# midimixer-channel-rev2.net
KiCad netlist of a schematic drawn in EAGLE
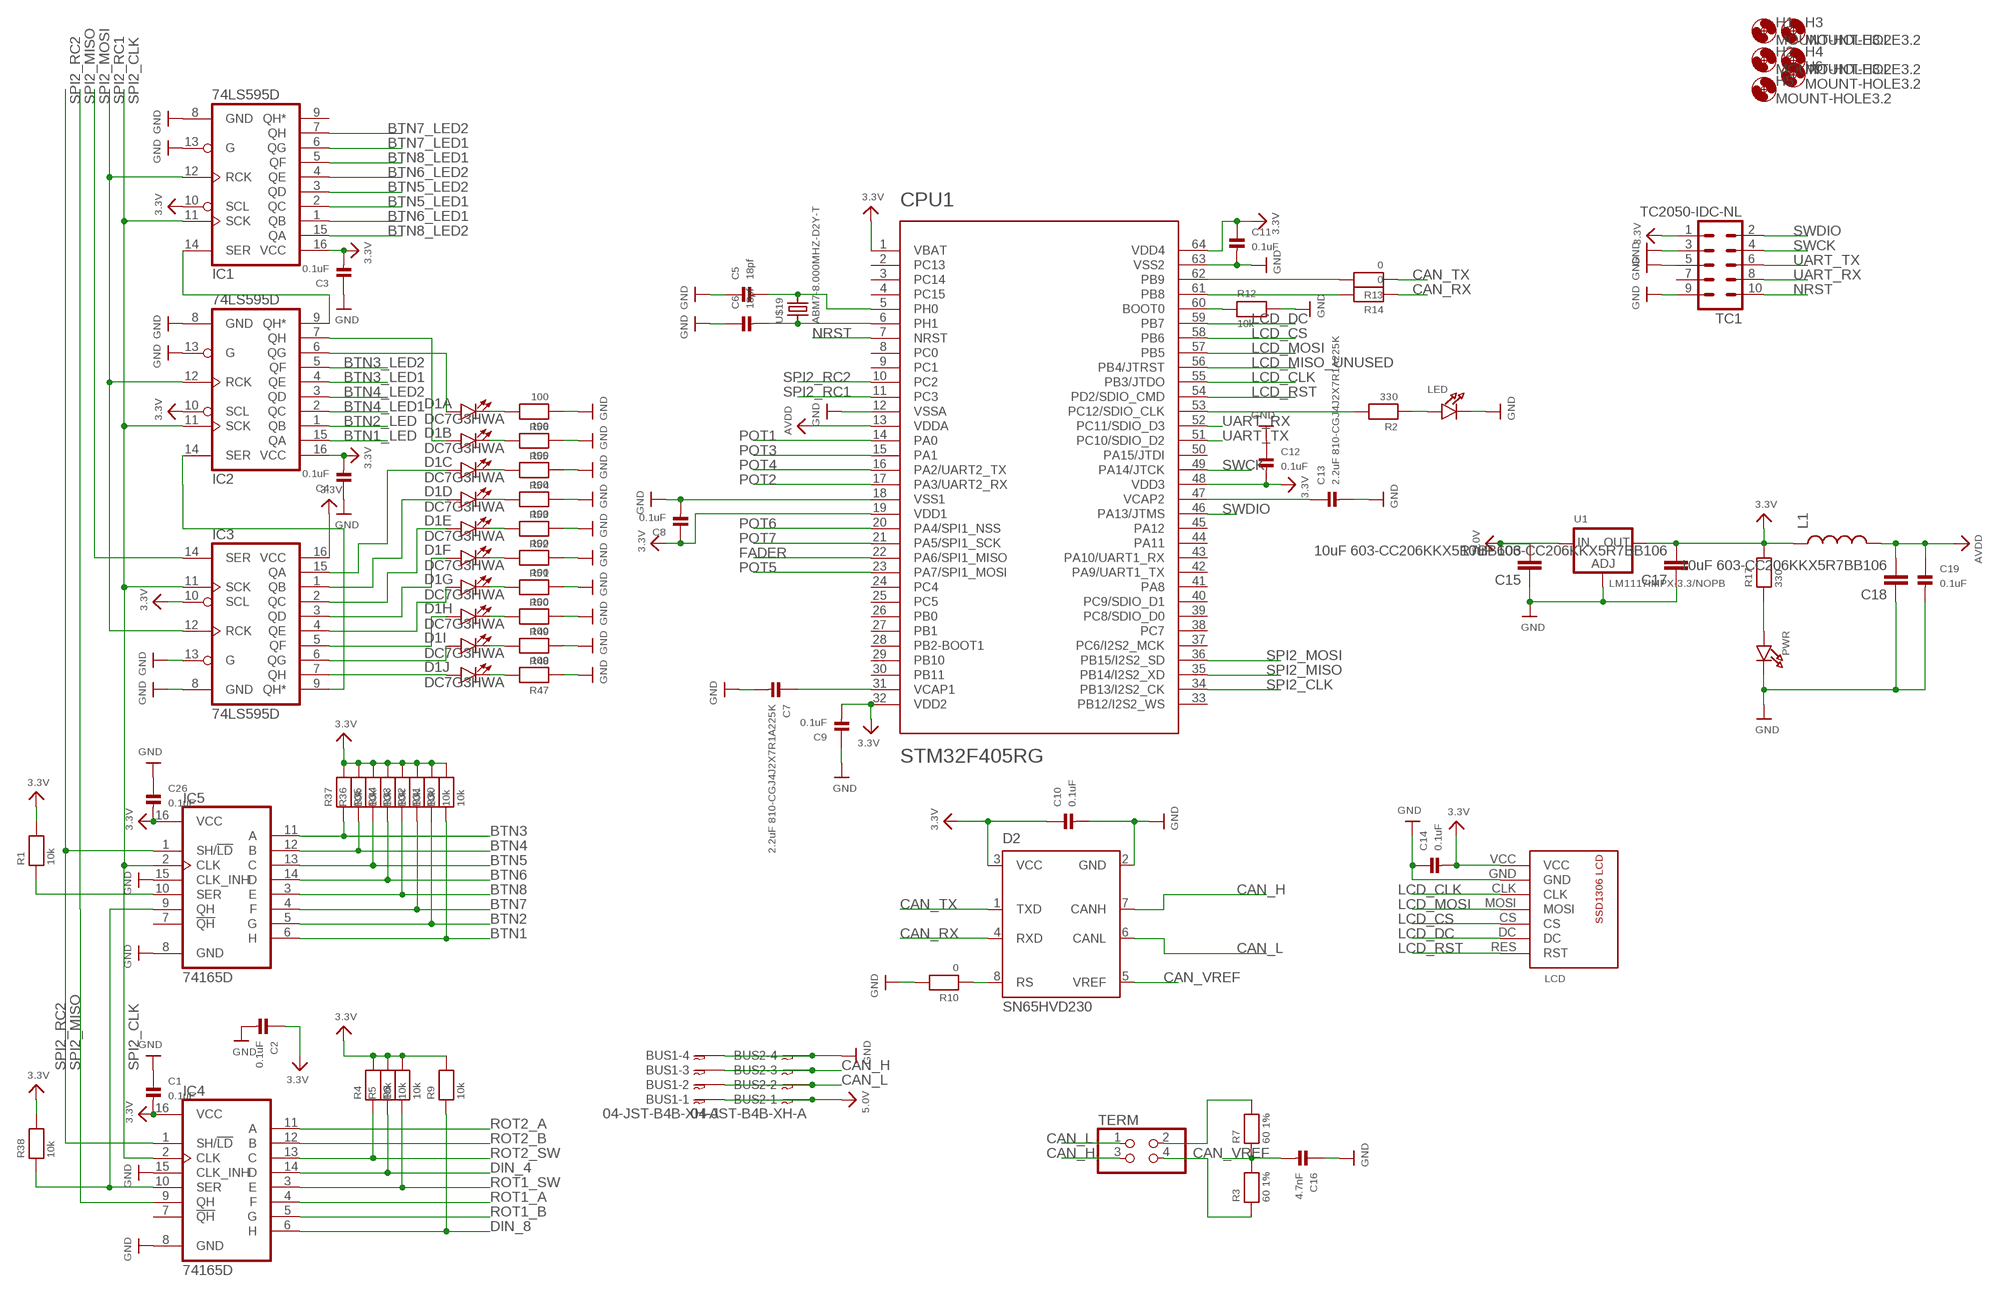
[diagram p0: schematic, sheet 1]
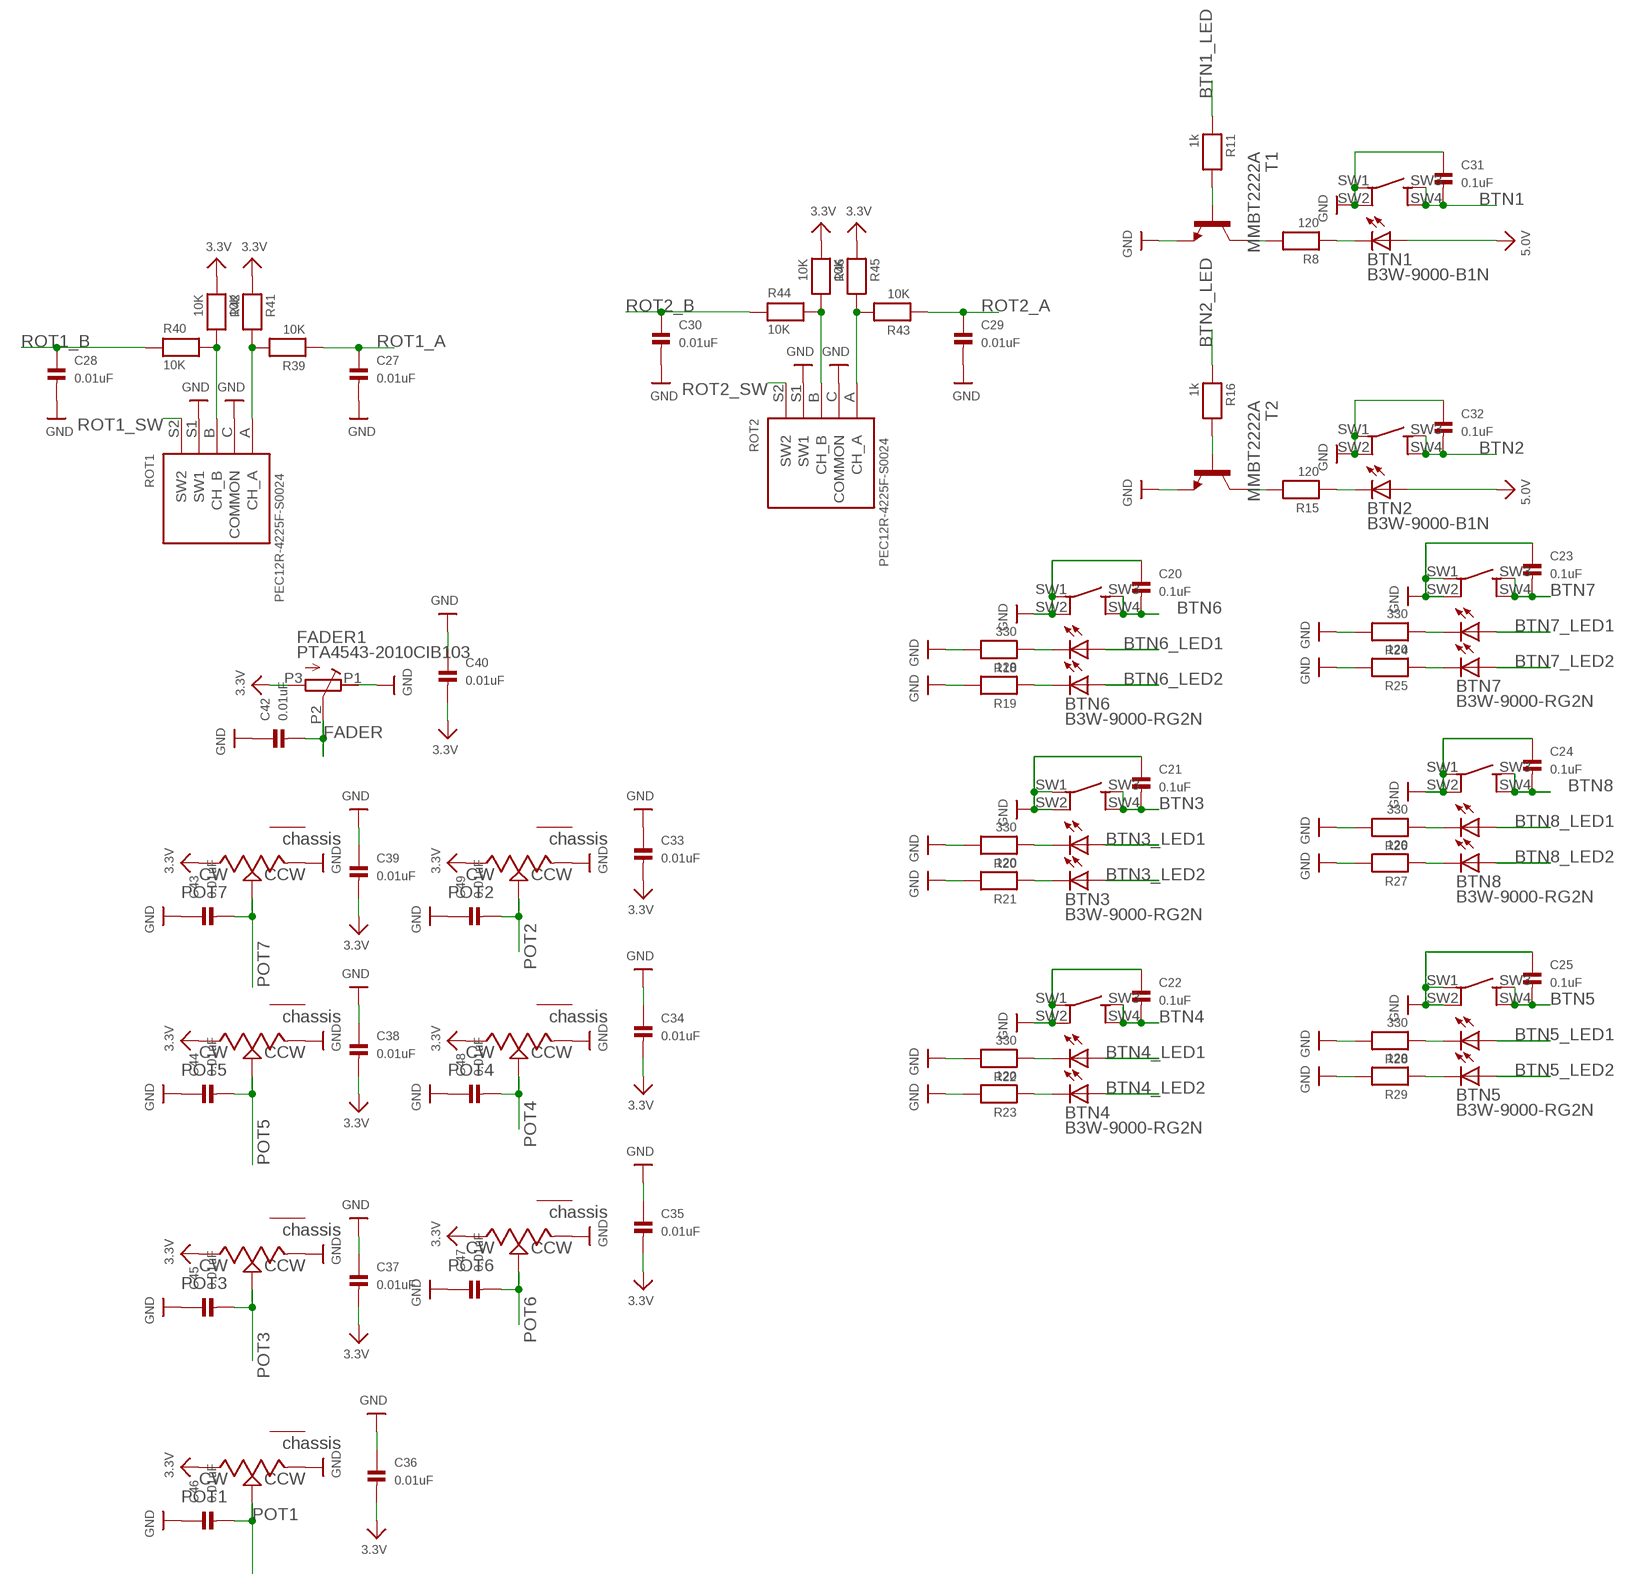
[diagram p1: schematic, sheet 2]

(export (version "E")
  (design (tool "Eeschema 10.0.6"))
  (components
    (comp (ref "BUS1")
      (value "04-JST-B4B-XH-A")
      (footprint "eagle-import:B4B-XH")
      (fields (field (name "MPN") "B4B-XH-A(LF)(SN)"))
      (libsource (lib "eagle-import") (part "04-JST-B4B-XH-A"))
    )
    (comp (ref "BUS2")
      (value "04-JST-B4B-XH-A")
      (footprint "eagle-import:B4B-XH")
      (fields (field (name "MPN") "B4B-XH-A(LF)(SN)"))
      (libsource (lib "eagle-import") (part "04-JST-B4B-XH-A"))
    )
    (comp (ref "C1")
      (value "0.1uF")
      (footprint "eagle-import:0603")
      (libsource (lib "eagle-import") (part "CAP_CERAMIC0603"))
    )
    (comp (ref "C2")
      (value "0.1uF")
      (footprint "eagle-import:0603")
      (libsource (lib "eagle-import") (part "CAP_CERAMIC0603"))
    )
    (comp (ref "C3")
      (value "0.1uF")
      (footprint "eagle-import:0603")
      (libsource (lib "eagle-import") (part "CAP_CERAMIC0603"))
    )
    (comp (ref "C4")
      (value "0.1uF")
      (footprint "eagle-import:0603")
      (libsource (lib "eagle-import") (part "CAP_CERAMIC0603"))
    )
    (comp (ref "C5")
      (value "18pf")
      (footprint "eagle-import:0603")
      (libsource (lib "eagle-import") (part "CAP_CERAMIC0603"))
    )
    (comp (ref "C6")
      (value "18pf")
      (footprint "eagle-import:0603")
      (libsource (lib "eagle-import") (part "CAP_CERAMIC0603"))
    )
    (comp (ref "C7")
      (value "2.2uF 810-CGJ4J2X7R1A225K")
      (footprint "eagle-import:0805")
      (fields (field (name "MPN") "CGJ4J2X7R1A225K125AA"))
      (libsource (lib "eagle-import") (part "CAP_CERAMIC0805"))
    )
    (comp (ref "C8")
      (value "0.1uF")
      (footprint "eagle-import:0603")
      (libsource (lib "eagle-import") (part "CAP_CERAMIC0603"))
    )
    (comp (ref "C9")
      (value "0.1uF")
      (footprint "eagle-import:0603")
      (libsource (lib "eagle-import") (part "CAP_CERAMIC0603"))
    )
    (comp (ref "C10")
      (value "0.1uF")
      (footprint "eagle-import:0603")
      (libsource (lib "eagle-import") (part "CAP_CERAMIC0603"))
    )
    (comp (ref "C11")
      (value "0.1uF")
      (footprint "eagle-import:0603")
      (libsource (lib "eagle-import") (part "CAP_CERAMIC0603"))
    )
    (comp (ref "C12")
      (value "0.1uF")
      (footprint "eagle-import:0603")
      (libsource (lib "eagle-import") (part "CAP_CERAMIC0603"))
    )
    (comp (ref "C13")
      (value "2.2uF 810-CGJ4J2X7R1A225K")
      (footprint "eagle-import:0805")
      (fields (field (name "MPN") "CGJ4J2X7R1A225K125AA"))
      (libsource (lib "eagle-import") (part "CAP_CERAMIC0805"))
    )
    (comp (ref "C14")
      (value "0.1uF")
      (footprint "eagle-import:0603")
      (libsource (lib "eagle-import") (part "CAP_CERAMIC0603"))
    )
    (comp (ref "C15")
      (value "10uF 603-CC206KKX5R7BB106")
      (footprint "eagle-import:1206")
      (fields (field (name "MPN") "CC1206KKX5R7BB106"))
      (libsource (lib "eagle-import") (part "CAP1206"))
    )
    (comp (ref "C16")
      (value "4.7nF")
      (footprint "eagle-import:0603")
      (libsource (lib "eagle-import") (part "CAP_CERAMIC0603"))
    )
    (comp (ref "C17")
      (value "10uF 603-CC206KKX5R7BB106")
      (footprint "eagle-import:1206")
      (fields (field (name "MPN") "CC1206KKX5R7BB106"))
      (libsource (lib "eagle-import") (part "CAP1206"))
    )
    (comp (ref "C18")
      (value "10uF 603-CC206KKX5R7BB106")
      (footprint "eagle-import:1206")
      (fields (field (name "MPN") "CC1206KKX5R7BB106"))
      (libsource (lib "eagle-import") (part "CAP1206"))
    )
    (comp (ref "C19")
      (value "0.1uF")
      (footprint "eagle-import:0603")
      (libsource (lib "eagle-import") (part "CAP_CERAMIC0603"))
    )
    (comp (ref "C26")
      (value "0.1uF")
      (footprint "eagle-import:0603")
      (libsource (lib "eagle-import") (part "CAP_CERAMIC0603"))
    )
    (comp (ref "CPU1")
      (value "STM32F405RG")
      (footprint "eagle-import:TQFP64")
      (fields (field (name "MPN") "STM32F405RGT6"))
      (libsource (lib "eagle-import") (part "STM32F405RG"))
    )
    (comp (ref "D1")
      (value "DC7G3HWA")
      (footprint "eagle-import:LED_BARGAPH_10")
      (libsource (lib "eagle-import") (part "LED_BARGRAPH_10"))
    )
    (comp (ref "D2")
      (value "SN65HVD230")
      (footprint "eagle-import:SO8")
      (fields (field (name "MPN") "SN65HVD230DR"))
      (libsource (lib "eagle-import") (part "SN65HVD230"))
    )
    (comp (ref "H1")
      (value "MOUNT-HOLE3.2")
      (footprint "eagle-import:3,2")
      (libsource (lib "eagle-import") (part "MOUNT-HOLE3.2"))
    )
    (comp (ref "H2")
      (value "MOUNT-HOLE3.2")
      (footprint "eagle-import:3,2")
      (libsource (lib "eagle-import") (part "MOUNT-HOLE3.2"))
    )
    (comp (ref "H3")
      (value "MOUNT-HOLE3.2")
      (footprint "eagle-import:3,2")
      (libsource (lib "eagle-import") (part "MOUNT-HOLE3.2"))
    )
    (comp (ref "H4")
      (value "MOUNT-HOLE3.2")
      (footprint "eagle-import:3,2")
      (libsource (lib "eagle-import") (part "MOUNT-HOLE3.2"))
    )
    (comp (ref "H5")
      (value "MOUNT-HOLE3.2")
      (footprint "eagle-import:3,2")
      (libsource (lib "eagle-import") (part "MOUNT-HOLE3.2"))
    )
    (comp (ref "H6")
      (value "MOUNT-HOLE3.2")
      (footprint "eagle-import:3,2")
      (libsource (lib "eagle-import") (part "MOUNT-HOLE3.2"))
    )
    (comp (ref "IC1")
      (value "74LS595D")
      (footprint "eagle-import:SO16")
      (fields (field (name "MPN") "74HC595D,118"))
      (libsource (lib "eagle-import") (part "74595DLS"))
    )
    (comp (ref "IC2")
      (value "74LS595D")
      (footprint "eagle-import:SO16")
      (fields (field (name "MPN") "74HC595D,118"))
      (libsource (lib "eagle-import") (part "74595DLS"))
    )
    (comp (ref "IC3")
      (value "74LS595D")
      (footprint "eagle-import:SO16")
      (fields (field (name "MPN") "74HC595D,118"))
      (libsource (lib "eagle-import") (part "74595DLS"))
    )
    (comp (ref "IC4")
      (value "74165D")
      (footprint "eagle-import:SO16")
      (fields (field (name "MPN") "74HC165D,653"))
      (libsource (lib "eagle-import") (part "74165D"))
    )
    (comp (ref "IC5")
      (value "74165D")
      (footprint "eagle-import:SO16")
      (fields (field (name "MPN") "74HC165D,653"))
      (libsource (lib "eagle-import") (part "74165D"))
    )
    (comp (ref "L1")
      (value "INDUCTOR0805")
      (footprint "eagle-import:0805")
      (fields (field (name "MPN") "2508056017Y2"))
      (libsource (lib "eagle-import") (part "INDUCTOR0805"))
    )
    (comp (ref "LCD")
      (value "SSD1306-7PINWITHOUT-HOLES")
      (footprint "eagle-import:SSD1306-7PIN-NO-HOLES")
      (libsource (lib "eagle-import") (part "SSD1306-7PINWITHOUT-HOLES"))
    )
    (comp (ref "LED")
      (value "LED0603")
      (footprint "eagle-import:CHIPLED_0603")
      (fields (field (name "MPN") "MF-LED-0603-GREEN"))
      (libsource (lib "eagle-import") (part "LED0603"))
    )
    (comp (ref "PWR")
      (value "LED0603")
      (footprint "eagle-import:CHIPLED_0603")
      (fields (field (name "MPN") "MF-LED-0603-GREEN"))
      (libsource (lib "eagle-import") (part "LED0603"))
    )
    (comp (ref "R1")
      (value "10k")
      (footprint "eagle-import:_0603")
      (libsource (lib "eagle-import") (part "RESISTOR_0603"))
    )
    (comp (ref "R2")
      (value "330")
      (footprint "eagle-import:0603")
      (libsource (lib "eagle-import") (part "RESISTOR0603"))
    )
    (comp (ref "R3")
      (value "60 1%")
      (footprint "eagle-import:0603")
      (fields (field (name "MPN") "MF-RES-0603-60.4"))
      (libsource (lib "eagle-import") (part "RESISTOR0603"))
    )
    (comp (ref "R4")
      (value "10k")
      (footprint "eagle-import:_0603")
      (libsource (lib "eagle-import") (part "RESISTOR_0603"))
    )
    (comp (ref "R5")
      (value "10k")
      (footprint "eagle-import:_0603")
      (libsource (lib "eagle-import") (part "RESISTOR_0603"))
    )
    (comp (ref "R6")
      (value "10k")
      (footprint "eagle-import:_0603")
      (libsource (lib "eagle-import") (part "RESISTOR_0603"))
    )
    (comp (ref "R7")
      (value "60 1%")
      (footprint "eagle-import:0603")
      (fields (field (name "MPN") "MF-RES-0603-60.4"))
      (libsource (lib "eagle-import") (part "RESISTOR0603"))
    )
    (comp (ref "R9")
      (value "10k")
      (footprint "eagle-import:_0603")
      (libsource (lib "eagle-import") (part "RESISTOR_0603"))
    )
    (comp (ref "R10")
      (value "0")
      (footprint "eagle-import:_0603")
      (libsource (lib "eagle-import") (part "RESISTOR_0603"))
    )
    (comp (ref "R12")
      (value "10k")
      (footprint "eagle-import:_0603")
      (libsource (lib "eagle-import") (part "RESISTOR_0603"))
    )
    (comp (ref "R13")
      (value "0")
      (footprint "eagle-import:_0603")
      (libsource (lib "eagle-import") (part "RESISTOR_0603"))
    )
    (comp (ref "R14")
      (value "0")
      (footprint "eagle-import:_0603")
      (libsource (lib "eagle-import") (part "RESISTOR_0603"))
    )
    (comp (ref "R17")
      (value "330")
      (footprint "eagle-import:0603")
      (libsource (lib "eagle-import") (part "RESISTOR0603"))
    )
    (comp (ref "R30")
      (value "10k")
      (footprint "eagle-import:_0603")
      (libsource (lib "eagle-import") (part "RESISTOR_0603"))
    )
    (comp (ref "R31")
      (value "10k")
      (footprint "eagle-import:_0603")
      (libsource (lib "eagle-import") (part "RESISTOR_0603"))
    )
    (comp (ref "R32")
      (value "10k")
      (footprint "eagle-import:_0603")
      (libsource (lib "eagle-import") (part "RESISTOR_0603"))
    )
    (comp (ref "R33")
      (value "10k")
      (footprint "eagle-import:_0603")
      (libsource (lib "eagle-import") (part "RESISTOR_0603"))
    )
    (comp (ref "R34")
      (value "10k")
      (footprint "eagle-import:_0603")
      (libsource (lib "eagle-import") (part "RESISTOR_0603"))
    )
    (comp (ref "R35")
      (value "10k")
      (footprint "eagle-import:_0603")
      (libsource (lib "eagle-import") (part "RESISTOR_0603"))
    )
    (comp (ref "R36")
      (value "10k")
      (footprint "eagle-import:_0603")
      (libsource (lib "eagle-import") (part "RESISTOR_0603"))
    )
    (comp (ref "R37")
      (value "10k")
      (footprint "eagle-import:_0603")
      (libsource (lib "eagle-import") (part "RESISTOR_0603"))
    )
    (comp (ref "R38")
      (value "10k")
      (footprint "eagle-import:_0603")
      (libsource (lib "eagle-import") (part "RESISTOR_0603"))
    )
    (comp (ref "R47")
      (value "100")
      (footprint "eagle-import:_0603")
      (libsource (lib "eagle-import") (part "RESISTOR_0603"))
    )
    (comp (ref "R48")
      (value "100")
      (footprint "eagle-import:_0603")
      (libsource (lib "eagle-import") (part "RESISTOR_0603"))
    )
    (comp (ref "R49")
      (value "100")
      (footprint "eagle-import:_0603")
      (libsource (lib "eagle-import") (part "RESISTOR_0603"))
    )
    (comp (ref "R50")
      (value "100")
      (footprint "eagle-import:_0603")
      (libsource (lib "eagle-import") (part "RESISTOR_0603"))
    )
    (comp (ref "R51")
      (value "100")
      (footprint "eagle-import:_0603")
      (libsource (lib "eagle-import") (part "RESISTOR_0603"))
    )
    (comp (ref "R52")
      (value "100")
      (footprint "eagle-import:_0603")
      (libsource (lib "eagle-import") (part "RESISTOR_0603"))
    )
    (comp (ref "R53")
      (value "100")
      (footprint "eagle-import:_0603")
      (libsource (lib "eagle-import") (part "RESISTOR_0603"))
    )
    (comp (ref "R54")
      (value "100")
      (footprint "eagle-import:_0603")
      (libsource (lib "eagle-import") (part "RESISTOR_0603"))
    )
    (comp (ref "R55")
      (value "100")
      (footprint "eagle-import:_0603")
      (libsource (lib "eagle-import") (part "RESISTOR_0603"))
    )
    (comp (ref "R56")
      (value "100")
      (footprint "eagle-import:_0603")
      (libsource (lib "eagle-import") (part "RESISTOR_0603"))
    )
    (comp (ref "TC1")
      (value "TC2050-IDC-NL")
      (footprint "eagle-import:TC2050-IDC-NL")
      (libsource (lib "eagle-import") (part "TC2050-IDC-NL"))
    )
    (comp (ref "TERM")
      (value "PINHD-2X2")
      (footprint "eagle-import:2X02")
      (fields (field (name "MPN") "5-146254-2"))
      (libsource (lib "eagle-import") (part "PINHD-2X2"))
    )
    (comp (ref "U$19")
      (value "ABM7-8.000MHZ-D2Y-T")
      (footprint "eagle-import:ABM7-8.000MHZ-D2Y-T")
      (libsource (lib "eagle-import") (part "ABM7-8.000MHZ-D2Y-T"))
    )
    (comp (ref "U1")
      (value "LM1117IMPX-3.3/NOPB")
      (footprint "eagle-import:SOT223-R")
      (fields (field (name "MPN") "LM1117MPX-3.3/NOPB"))
      (libsource (lib "eagle-import") (part "LM1117SOT223-REFLOW"))
    )
    (comp (ref "BTN1")
      (value "B3W-9000-B1N")
      (footprint "eagle-import:B3W-9000-X1X")
      (libsource (lib "eagle-import") (part "B3W-9000-B1N"))
    )
    (comp (ref "BTN2")
      (value "B3W-9000-B1N")
      (footprint "eagle-import:B3W-9000-X1X")
      (libsource (lib "eagle-import") (part "B3W-9000-B1N"))
    )
    (comp (ref "BTN3")
      (value "B3W-9000-RG2N")
      (footprint "eagle-import:B3W-9000-X2X")
      (libsource (lib "eagle-import") (part "B3W-9000-RG2N"))
    )
    (comp (ref "BTN4")
      (value "B3W-9000-RG2N")
      (footprint "eagle-import:B3W-9000-X2X")
      (libsource (lib "eagle-import") (part "B3W-9000-RG2N"))
    )
    (comp (ref "BTN5")
      (value "B3W-9000-RG2N")
      (footprint "eagle-import:B3W-9000-X2X")
      (libsource (lib "eagle-import") (part "B3W-9000-RG2N"))
    )
    (comp (ref "BTN6")
      (value "B3W-9000-RG2N")
      (footprint "eagle-import:B3W-9000-X2X")
      (libsource (lib "eagle-import") (part "B3W-9000-RG2N"))
    )
    (comp (ref "BTN7")
      (value "B3W-9000-RG2N")
      (footprint "eagle-import:B3W-9000-X2X")
      (libsource (lib "eagle-import") (part "B3W-9000-RG2N"))
    )
    (comp (ref "BTN8")
      (value "B3W-9000-RG2N")
      (footprint "eagle-import:B3W-9000-X2X")
      (libsource (lib "eagle-import") (part "B3W-9000-RG2N"))
    )
    (comp (ref "C20")
      (value "0.1uF")
      (footprint "eagle-import:0603")
      (libsource (lib "eagle-import") (part "CAP_CERAMIC0603"))
    )
    (comp (ref "C21")
      (value "0.1uF")
      (footprint "eagle-import:0603")
      (libsource (lib "eagle-import") (part "CAP_CERAMIC0603"))
    )
    (comp (ref "C22")
      (value "0.1uF")
      (footprint "eagle-import:0603")
      (libsource (lib "eagle-import") (part "CAP_CERAMIC0603"))
    )
    (comp (ref "C23")
      (value "0.1uF")
      (footprint "eagle-import:0603")
      (libsource (lib "eagle-import") (part "CAP_CERAMIC0603"))
    )
    (comp (ref "C24")
      (value "0.1uF")
      (footprint "eagle-import:0603")
      (libsource (lib "eagle-import") (part "CAP_CERAMIC0603"))
    )
    (comp (ref "C25")
      (value "0.1uF")
      (footprint "eagle-import:0603")
      (libsource (lib "eagle-import") (part "CAP_CERAMIC0603"))
    )
    (comp (ref "C27")
      (value "0.01uF")
      (footprint "eagle-import:0603")
      (libsource (lib "eagle-import") (part "CAP_CERAMIC0603"))
    )
    (comp (ref "C28")
      (value "0.01uF")
      (footprint "eagle-import:0603")
      (libsource (lib "eagle-import") (part "CAP_CERAMIC0603"))
    )
    (comp (ref "C29")
      (value "0.01uF")
      (footprint "eagle-import:0603")
      (libsource (lib "eagle-import") (part "CAP_CERAMIC0603"))
    )
    (comp (ref "C30")
      (value "0.01uF")
      (footprint "eagle-import:0603")
      (libsource (lib "eagle-import") (part "CAP_CERAMIC0603"))
    )
    (comp (ref "C31")
      (value "0.1uF")
      (footprint "eagle-import:0603")
      (libsource (lib "eagle-import") (part "CAP_CERAMIC0603"))
    )
    (comp (ref "C32")
      (value "0.1uF")
      (footprint "eagle-import:0603")
      (libsource (lib "eagle-import") (part "CAP_CERAMIC0603"))
    )
    (comp (ref "C33")
      (value "0.01uF")
      (footprint "eagle-import:0603")
      (libsource (lib "eagle-import") (part "CAP_CERAMIC0603"))
    )
    (comp (ref "C34")
      (value "0.01uF")
      (footprint "eagle-import:0603")
      (libsource (lib "eagle-import") (part "CAP_CERAMIC0603"))
    )
    (comp (ref "C35")
      (value "0.01uF")
      (footprint "eagle-import:0603")
      (libsource (lib "eagle-import") (part "CAP_CERAMIC0603"))
    )
    (comp (ref "C36")
      (value "0.01uF")
      (footprint "eagle-import:0603")
      (libsource (lib "eagle-import") (part "CAP_CERAMIC0603"))
    )
    (comp (ref "C37")
      (value "0.01uF")
      (footprint "eagle-import:0603")
      (libsource (lib "eagle-import") (part "CAP_CERAMIC0603"))
    )
    (comp (ref "C38")
      (value "0.01uF")
      (footprint "eagle-import:0603")
      (libsource (lib "eagle-import") (part "CAP_CERAMIC0603"))
    )
    (comp (ref "C39")
      (value "0.01uF")
      (footprint "eagle-import:0603")
      (libsource (lib "eagle-import") (part "CAP_CERAMIC0603"))
    )
    (comp (ref "C40")
      (value "0.01uF")
      (footprint "eagle-import:0603")
      (libsource (lib "eagle-import") (part "CAP_CERAMIC0603"))
    )
    (comp (ref "C42")
      (value "0.01uF")
      (footprint "eagle-import:0603")
      (libsource (lib "eagle-import") (part "CAP_CERAMIC0603"))
    )
    (comp (ref "C43")
      (value "0.01uF")
      (footprint "eagle-import:0603")
      (libsource (lib "eagle-import") (part "CAP_CERAMIC0603"))
    )
    (comp (ref "C44")
      (value "0.01uF")
      (footprint "eagle-import:0603")
      (libsource (lib "eagle-import") (part "CAP_CERAMIC0603"))
    )
    (comp (ref "C45")
      (value "0.01uF")
      (footprint "eagle-import:0603")
      (libsource (lib "eagle-import") (part "CAP_CERAMIC0603"))
    )
    (comp (ref "C46")
      (value "0.01uF")
      (footprint "eagle-import:0603")
      (libsource (lib "eagle-import") (part "CAP_CERAMIC0603"))
    )
    (comp (ref "C47")
      (value "0.01uF")
      (footprint "eagle-import:0603")
      (libsource (lib "eagle-import") (part "CAP_CERAMIC0603"))
    )
    (comp (ref "C48")
      (value "0.01uF")
      (footprint "eagle-import:0603")
      (libsource (lib "eagle-import") (part "CAP_CERAMIC0603"))
    )
    (comp (ref "C49")
      (value "0.01uF")
      (footprint "eagle-import:0603")
      (libsource (lib "eagle-import") (part "CAP_CERAMIC0603"))
    )
    (comp (ref "FADER1")
      (value "PTA4543-2010CIB103")
      (footprint "eagle-import:PTA4543-2015CPB103")
      (libsource (lib "eagle-import") (part "PTA4543-2015CPB103"))
    )
    (comp (ref "POT1")
      (value "POTENTIOMETERPTV09A_VERTICAL")
      (footprint "eagle-import:PTV09A-4")
      (fields (field (name "MPN") "PTV09A-4225F-B203"))
      (libsource (lib "eagle-import") (part "POTENTIOMETERPTV09A_VERTICAL"))
    )
    (comp (ref "POT2")
      (value "POTENTIOMETERPTV09A_VERTICAL")
      (footprint "eagle-import:PTV09A-4")
      (fields (field (name "MPN") "PTV09A-4225F-B203"))
      (libsource (lib "eagle-import") (part "POTENTIOMETERPTV09A_VERTICAL"))
    )
    (comp (ref "POT3")
      (value "POTENTIOMETERPTV09A_VERTICAL")
      (footprint "eagle-import:PTV09A-4")
      (fields (field (name "MPN") "PTV09A-4225F-B203"))
      (libsource (lib "eagle-import") (part "POTENTIOMETERPTV09A_VERTICAL"))
    )
    (comp (ref "POT4")
      (value "POTENTIOMETERPTV09A_VERTICAL")
      (footprint "eagle-import:PTV09A-4")
      (fields (field (name "MPN") "PTV09A-4225F-B203"))
      (libsource (lib "eagle-import") (part "POTENTIOMETERPTV09A_VERTICAL"))
    )
    (comp (ref "POT5")
      (value "POTENTIOMETERPTV09A_VERTICAL")
      (footprint "eagle-import:PTV09A-4")
      (fields (field (name "MPN") "PTV09A-4225F-B203"))
      (libsource (lib "eagle-import") (part "POTENTIOMETERPTV09A_VERTICAL"))
    )
    (comp (ref "POT6")
      (value "POTENTIOMETERPTV09A_VERTICAL")
      (footprint "eagle-import:PTV09A-4")
      (fields (field (name "MPN") "PTV09A-4225F-B203"))
      (libsource (lib "eagle-import") (part "POTENTIOMETERPTV09A_VERTICAL"))
    )
    (comp (ref "POT7")
      (value "POTENTIOMETERPTV09A_VERTICAL")
      (footprint "eagle-import:PTV09A-4")
      (fields (field (name "MPN") "PTV09A-4225F-B203"))
      (libsource (lib "eagle-import") (part "POTENTIOMETERPTV09A_VERTICAL"))
    )
    (comp (ref "R8")
      (value "120")
      (footprint "eagle-import:0603")
      (libsource (lib "eagle-import") (part "RESISTOR0603"))
    )
    (comp (ref "R11")
      (value "1k")
      (footprint "eagle-import:0603")
      (libsource (lib "eagle-import") (part "RESISTOR0603"))
    )
    (comp (ref "R15")
      (value "120")
      (footprint "eagle-import:0603")
      (libsource (lib "eagle-import") (part "RESISTOR0603"))
    )
    (comp (ref "R16")
      (value "1k")
      (footprint "eagle-import:0603")
      (libsource (lib "eagle-import") (part "RESISTOR0603"))
    )
    (comp (ref "R18")
      (value "330")
      (footprint "eagle-import:0603")
      (libsource (lib "eagle-import") (part "RESISTOR0603"))
    )
    (comp (ref "R19")
      (value "120")
      (footprint "eagle-import:0603")
      (libsource (lib "eagle-import") (part "RESISTOR0603"))
    )
    (comp (ref "R20")
      (value "330")
      (footprint "eagle-import:0603")
      (libsource (lib "eagle-import") (part "RESISTOR0603"))
    )
    (comp (ref "R21")
      (value "120")
      (footprint "eagle-import:0603")
      (libsource (lib "eagle-import") (part "RESISTOR0603"))
    )
    (comp (ref "R22")
      (value "330")
      (footprint "eagle-import:0603")
      (libsource (lib "eagle-import") (part "RESISTOR0603"))
    )
    (comp (ref "R23")
      (value "120")
      (footprint "eagle-import:0603")
      (libsource (lib "eagle-import") (part "RESISTOR0603"))
    )
    (comp (ref "R24")
      (value "330")
      (footprint "eagle-import:0603")
      (libsource (lib "eagle-import") (part "RESISTOR0603"))
    )
    (comp (ref "R25")
      (value "120")
      (footprint "eagle-import:0603")
      (libsource (lib "eagle-import") (part "RESISTOR0603"))
    )
    (comp (ref "R26")
      (value "330")
      (footprint "eagle-import:0603")
      (libsource (lib "eagle-import") (part "RESISTOR0603"))
    )
    (comp (ref "R27")
      (value "120")
      (footprint "eagle-import:0603")
      (libsource (lib "eagle-import") (part "RESISTOR0603"))
    )
    (comp (ref "R28")
      (value "330")
      (footprint "eagle-import:0603")
      (libsource (lib "eagle-import") (part "RESISTOR0603"))
    )
    (comp (ref "R29")
      (value "120")
      (footprint "eagle-import:0603")
      (libsource (lib "eagle-import") (part "RESISTOR0603"))
    )
    (comp (ref "R39")
      (value "10K")
      (footprint "eagle-import:0603")
      (libsource (lib "eagle-import") (part "RESISTOR0603"))
    )
    (comp (ref "R40")
      (value "10K")
      (footprint "eagle-import:0603")
      (libsource (lib "eagle-import") (part "RESISTOR0603"))
    )
    (comp (ref "R41")
      (value "10K")
      (footprint "eagle-import:0603")
      (libsource (lib "eagle-import") (part "RESISTOR0603"))
    )
    (comp (ref "R42")
      (value "10K")
      (footprint "eagle-import:0603")
      (libsource (lib "eagle-import") (part "RESISTOR0603"))
    )
    (comp (ref "R43")
      (value "10K")
      (footprint "eagle-import:0603")
      (libsource (lib "eagle-import") (part "RESISTOR0603"))
    )
    (comp (ref "R44")
      (value "10K")
      (footprint "eagle-import:0603")
      (libsource (lib "eagle-import") (part "RESISTOR0603"))
    )
    (comp (ref "R45")
      (value "10K")
      (footprint "eagle-import:0603")
      (libsource (lib "eagle-import") (part "RESISTOR0603"))
    )
    (comp (ref "R46")
      (value "10K")
      (footprint "eagle-import:0603")
      (libsource (lib "eagle-import") (part "RESISTOR0603"))
    )
    (comp (ref "ROT1")
      (value "PEC12R-4225F-S0024")
      (footprint "eagle-import:PEC111-4XXXK-SXXXX")
      (libsource (lib "eagle-import") (part "PEC11-4215K-S0024"))
    )
    (comp (ref "ROT2")
      (value "PEC12R-4225F-S0024")
      (footprint "eagle-import:PEC111-4XXXK-SXXXX")
      (libsource (lib "eagle-import") (part "PEC11-4215K-S0024"))
    )
    (comp (ref "T1")
      (value "MMBT2222A")
      (footprint "eagle-import:SOT23-BEC")
      (libsource (lib "eagle-import") (part "-NPN-SOT23-BECMMBT2222ALT1"))
    )
    (comp (ref "T2")
      (value "MMBT2222A")
      (footprint "eagle-import:SOT23-BEC")
      (libsource (lib "eagle-import") (part "-NPN-SOT23-BECMMBT2222ALT1"))
    )
  )
  (nets
    (net (code "1") (name "3.3V") (class "Default")
      (node (ref "C1") (pin "2") (pinfunction "P$2_2") (pintype "passive"))
      (node (ref "C10") (pin "1") (pinfunction "P$1_1") (pintype "passive"))
      (node (ref "C11") (pin "1") (pinfunction "P$1_1") (pintype "passive"))
      (node (ref "C12") (pin "2") (pinfunction "P$2_2") (pintype "passive"))
      (node (ref "C14") (pin "2") (pinfunction "P$2_2") (pintype "passive"))
      (node (ref "C17") (pin "2") (pinfunction "2_2") (pintype "passive"))
      (node (ref "C2") (pin "1") (pinfunction "P$1_1") (pintype "passive"))
      (node (ref "C26") (pin "2") (pinfunction "P$2_2") (pintype "passive"))
      (node (ref "C3") (pin "2") (pinfunction "P$2_2") (pintype "passive"))
      (node (ref "C33") (pin "2") (pinfunction "P$2_2") (pintype "passive"))
      (node (ref "C34") (pin "2") (pinfunction "P$2_2") (pintype "passive"))
      (node (ref "C35") (pin "2") (pinfunction "P$2_2") (pintype "passive"))
      (node (ref "C36") (pin "2") (pinfunction "P$2_2") (pintype "passive"))
      (node (ref "C37") (pin "2") (pinfunction "P$2_2") (pintype "passive"))
      (node (ref "C38") (pin "2") (pinfunction "P$2_2") (pintype "passive"))
      (node (ref "C39") (pin "2") (pinfunction "P$2_2") (pintype "passive"))
      (node (ref "C4") (pin "2") (pinfunction "P$2_2") (pintype "passive"))
      (node (ref "C40") (pin "2") (pinfunction "P$2_2") (pintype "passive"))
      (node (ref "C8") (pin "1") (pinfunction "P$1_1") (pintype "passive"))
      (node (ref "C9") (pin "2") (pinfunction "P$2_2") (pintype "passive"))
      (node (ref "CPU1") (pin "1") (pinfunction "VBAT_1") (pintype "bidirectional"))
      (node (ref "CPU1") (pin "19") (pinfunction "VDD1_19") (pintype "bidirectional"))
      (node (ref "CPU1") (pin "32") (pinfunction "VDD2_32") (pintype "bidirectional"))
      (node (ref "CPU1") (pin "48") (pinfunction "VDD3_48") (pintype "bidirectional"))
      (node (ref "CPU1") (pin "64") (pinfunction "VDD4_64") (pintype "bidirectional"))
      (node (ref "D2") (pin "3") (pinfunction "VCC_3") (pintype "power_in"))
      (node (ref "FADER1") (pin "P3") (pinfunction "E_P3") (pintype "passive"))
      (node (ref "IC1") (pin "10") (pinfunction "SCL_10") (pintype "input"))
      (node (ref "IC1") (pin "16") (pinfunction "VCC_16") (pintype "power_in"))
      (node (ref "IC2") (pin "10") (pinfunction "SCL_10") (pintype "input"))
      (node (ref "IC2") (pin "16") (pinfunction "VCC_16") (pintype "power_in"))
      (node (ref "IC3") (pin "10") (pinfunction "SCL_10") (pintype "input"))
      (node (ref "IC3") (pin "16") (pinfunction "VCC_16") (pintype "power_in"))
      (node (ref "IC4") (pin "16") (pinfunction "VCC_16") (pintype "power_in"))
      (node (ref "IC5") (pin "16") (pinfunction "VCC_16") (pintype "power_in"))
      (node (ref "L1") (pin "1") (pinfunction "1_1") (pintype "passive"))
      (node (ref "LCD") (pin "VCC") (pinfunction "VCC_VCC") (pintype "bidirectional"))
      (node (ref "POT1") (pin "CW") (pinfunction "CW_CW") (pintype "passive"))
      (node (ref "POT2") (pin "CW") (pinfunction "CW_CW") (pintype "passive"))
      (node (ref "POT3") (pin "CW") (pinfunction "CW_CW") (pintype "passive"))
      (node (ref "POT4") (pin "CW") (pinfunction "CW_CW") (pintype "passive"))
      (node (ref "POT5") (pin "CW") (pinfunction "CW_CW") (pintype "passive"))
      (node (ref "POT6") (pin "CW") (pinfunction "CW_CW") (pintype "passive"))
      (node (ref "POT7") (pin "CW") (pinfunction "CW_CW") (pintype "passive"))
      (node (ref "R1") (pin "2") (pinfunction "2_2") (pintype "passive"))
      (node (ref "R17") (pin "2") (pinfunction "2_2") (pintype "passive"))
      (node (ref "R30") (pin "2") (pinfunction "2_2") (pintype "passive"))
      (node (ref "R31") (pin "2") (pinfunction "2_2") (pintype "passive"))
      (node (ref "R32") (pin "2") (pinfunction "2_2") (pintype "passive"))
      (node (ref "R33") (pin "2") (pinfunction "2_2") (pintype "passive"))
      (node (ref "R34") (pin "2") (pinfunction "2_2") (pintype "passive"))
      (node (ref "R35") (pin "2") (pinfunction "2_2") (pintype "passive"))
      (node (ref "R36") (pin "2") (pinfunction "2_2") (pintype "passive"))
      (node (ref "R37") (pin "2") (pinfunction "2_2") (pintype "passive"))
      (node (ref "R38") (pin "2") (pinfunction "2_2") (pintype "passive"))
      (node (ref "R4") (pin "2") (pinfunction "2_2") (pintype "passive"))
      (node (ref "R41") (pin "1") (pinfunction "1_1") (pintype "passive"))
      (node (ref "R42") (pin "1") (pinfunction "1_1") (pintype "passive"))
      (node (ref "R45") (pin "1") (pinfunction "1_1") (pintype "passive"))
      (node (ref "R46") (pin "1") (pinfunction "1_1") (pintype "passive"))
      (node (ref "R5") (pin "2") (pinfunction "2_2") (pintype "passive"))
      (node (ref "R6") (pin "2") (pinfunction "2_2") (pintype "passive"))
      (node (ref "R9") (pin "2") (pinfunction "2_2") (pintype "passive"))
      (node (ref "TC1") (pin "1") (pinfunction "1_1") (pintype "passive"))
      (node (ref "U1") (pin "2") (pinfunction "OUT_2") (pintype "passive"))
    )
    (net (code "2") (name "5.0V") (class "Default")
      (node (ref "BTN1") (pin "LED1+") (pinfunction "LED1+_LED1+") (pintype "passive"))
      (node (ref "BTN2") (pin "LED1+") (pinfunction "LED1+_LED1+") (pintype "passive"))
      (node (ref "BUS1") (pin "P$1") (pinfunction "1_P$1") (pintype "passive"))
      (node (ref "BUS2") (pin "P$1") (pinfunction "1_P$1") (pintype "passive"))
      (node (ref "C15") (pin "2") (pinfunction "2_2") (pintype "passive"))
      (node (ref "U1") (pin "3") (pinfunction "IN_3") (pintype "input"))
    )
    (net (code "3") (name "AVDD") (class "Default")
      (node (ref "C18") (pin "2") (pinfunction "2_2") (pintype "passive"))
      (node (ref "C19") (pin "1") (pinfunction "P$1_1") (pintype "passive"))
      (node (ref "CPU1") (pin "13") (pinfunction "VDDA_13") (pintype "bidirectional"))
      (node (ref "L1") (pin "2") (pinfunction "2_2") (pintype "passive"))
    )
    (net (code "4") (name "BTN1") (class "Default")
      (node (ref "BTN1") (pin "SW3") (pinfunction "SW2_A_SW3") (pintype "passive"))
      (node (ref "BTN1") (pin "SW4") (pinfunction "SW2_B_SW4") (pintype "passive"))
      (node (ref "C31") (pin "2") (pinfunction "P$2_2") (pintype "passive"))
      (node (ref "IC5") (pin "6") (pinfunction "H_6") (pintype "tri_state"))
      (node (ref "R30") (pin "1") (pinfunction "1_1") (pintype "passive"))
    )
    (net (code "5") (name "BTN1_LED") (class "Default")
      (node (ref "IC2") (pin "15") (pinfunction "QA_15") (pintype "tri_state"))
      (node (ref "R11") (pin "1") (pinfunction "1_1") (pintype "passive"))
    )
    (net (code "6") (name "BTN2") (class "Default")
      (node (ref "BTN2") (pin "SW3") (pinfunction "SW2_A_SW3") (pintype "passive"))
      (node (ref "BTN2") (pin "SW4") (pinfunction "SW2_B_SW4") (pintype "passive"))
      (node (ref "C32") (pin "2") (pinfunction "P$2_2") (pintype "passive"))
      (node (ref "IC5") (pin "5") (pinfunction "G_5") (pintype "tri_state"))
      (node (ref "R31") (pin "1") (pinfunction "1_1") (pintype "passive"))
    )
    (net (code "7") (name "BTN2_LED") (class "Default")
      (node (ref "IC2") (pin "1") (pinfunction "QB_1") (pintype "tri_state"))
      (node (ref "R16") (pin "1") (pinfunction "1_1") (pintype "passive"))
    )
    (net (code "8") (name "BTN3") (class "Default")
      (node (ref "BTN3") (pin "SW3") (pinfunction "SW2_A_SW3") (pintype "passive"))
      (node (ref "BTN3") (pin "SW4") (pinfunction "SW2_B_SW4") (pintype "passive"))
      (node (ref "C21") (pin "2") (pinfunction "P$2_2") (pintype "passive"))
      (node (ref "IC5") (pin "11") (pinfunction "A_11") (pintype "tri_state"))
      (node (ref "R37") (pin "1") (pinfunction "1_1") (pintype "passive"))
    )
    (net (code "9") (name "BTN3_LED1") (class "Default")
      (node (ref "BTN3") (pin "LED1+") (pinfunction "LED1+_LED1+") (pintype "passive"))
      (node (ref "IC2") (pin "4") (pinfunction "QE_4") (pintype "tri_state"))
    )
    (net (code "10") (name "BTN3_LED2") (class "Default")
      (node (ref "BTN3") (pin "LED2+") (pinfunction "LED2+_LED2+") (pintype "passive"))
      (node (ref "IC2") (pin "5") (pinfunction "QF_5") (pintype "tri_state"))
    )
    (net (code "11") (name "BTN4") (class "Default")
      (node (ref "BTN4") (pin "SW3") (pinfunction "SW2_A_SW3") (pintype "passive"))
      (node (ref "BTN4") (pin "SW4") (pinfunction "SW2_B_SW4") (pintype "passive"))
      (node (ref "C22") (pin "2") (pinfunction "P$2_2") (pintype "passive"))
      (node (ref "IC5") (pin "12") (pinfunction "B_12") (pintype "tri_state"))
      (node (ref "R36") (pin "1") (pinfunction "1_1") (pintype "passive"))
    )
    (net (code "12") (name "BTN4_LED1") (class "Default")
      (node (ref "BTN4") (pin "LED1+") (pinfunction "LED1+_LED1+") (pintype "passive"))
      (node (ref "IC2") (pin "2") (pinfunction "QC_2") (pintype "tri_state"))
    )
    (net (code "13") (name "BTN4_LED2") (class "Default")
      (node (ref "BTN4") (pin "LED2+") (pinfunction "LED2+_LED2+") (pintype "passive"))
      (node (ref "IC2") (pin "3") (pinfunction "QD_3") (pintype "tri_state"))
    )
    (net (code "14") (name "BTN5") (class "Default")
      (node (ref "BTN5") (pin "SW3") (pinfunction "SW2_A_SW3") (pintype "passive"))
      (node (ref "BTN5") (pin "SW4") (pinfunction "SW2_B_SW4") (pintype "passive"))
      (node (ref "C25") (pin "2") (pinfunction "P$2_2") (pintype "passive"))
      (node (ref "IC5") (pin "13") (pinfunction "C_13") (pintype "tri_state"))
      (node (ref "R35") (pin "1") (pinfunction "1_1") (pintype "passive"))
    )
    (net (code "15") (name "BTN5_LED1") (class "Default")
      (node (ref "BTN5") (pin "LED1+") (pinfunction "LED1+_LED1+") (pintype "passive"))
      (node (ref "IC1") (pin "2") (pinfunction "QC_2") (pintype "tri_state"))
    )
    (net (code "16") (name "BTN5_LED2") (class "Default")
      (node (ref "BTN5") (pin "LED2+") (pinfunction "LED2+_LED2+") (pintype "passive"))
      (node (ref "IC1") (pin "3") (pinfunction "QD_3") (pintype "tri_state"))
    )
    (net (code "17") (name "BTN6") (class "Default")
      (node (ref "BTN6") (pin "SW3") (pinfunction "SW2_A_SW3") (pintype "passive"))
      (node (ref "BTN6") (pin "SW4") (pinfunction "SW2_B_SW4") (pintype "passive"))
      (node (ref "C20") (pin "2") (pinfunction "P$2_2") (pintype "passive"))
      (node (ref "IC5") (pin "14") (pinfunction "D_14") (pintype "tri_state"))
      (node (ref "R34") (pin "1") (pinfunction "1_1") (pintype "passive"))
    )
    (net (code "18") (name "BTN6_LED1") (class "Default")
      (node (ref "BTN6") (pin "LED1+") (pinfunction "LED1+_LED1+") (pintype "passive"))
      (node (ref "IC1") (pin "1") (pinfunction "QB_1") (pintype "tri_state"))
    )
    (net (code "19") (name "BTN6_LED2") (class "Default")
      (node (ref "BTN6") (pin "LED2+") (pinfunction "LED2+_LED2+") (pintype "passive"))
      (node (ref "IC1") (pin "4") (pinfunction "QE_4") (pintype "tri_state"))
    )
    (net (code "20") (name "BTN7") (class "Default")
      (node (ref "BTN7") (pin "SW3") (pinfunction "SW2_A_SW3") (pintype "passive"))
      (node (ref "BTN7") (pin "SW4") (pinfunction "SW2_B_SW4") (pintype "passive"))
      (node (ref "C23") (pin "2") (pinfunction "P$2_2") (pintype "passive"))
      (node (ref "IC5") (pin "4") (pinfunction "F_4") (pintype "tri_state"))
      (node (ref "R32") (pin "1") (pinfunction "1_1") (pintype "passive"))
    )
    (net (code "21") (name "BTN7_LED1") (class "Default")
      (node (ref "BTN7") (pin "LED1+") (pinfunction "LED1+_LED1+") (pintype "passive"))
      (node (ref "IC1") (pin "6") (pinfunction "QG_6") (pintype "tri_state"))
    )
    (net (code "22") (name "BTN7_LED2") (class "Default")
      (node (ref "BTN7") (pin "LED2+") (pinfunction "LED2+_LED2+") (pintype "passive"))
      (node (ref "IC1") (pin "7") (pinfunction "QH_7") (pintype "tri_state"))
    )
    (net (code "23") (name "BTN8") (class "Default")
      (node (ref "BTN8") (pin "SW3") (pinfunction "SW2_A_SW3") (pintype "passive"))
      (node (ref "BTN8") (pin "SW4") (pinfunction "SW2_B_SW4") (pintype "passive"))
      (node (ref "C24") (pin "2") (pinfunction "P$2_2") (pintype "passive"))
      (node (ref "IC5") (pin "3") (pinfunction "E_3") (pintype "tri_state"))
      (node (ref "R33") (pin "1") (pinfunction "1_1") (pintype "passive"))
    )
    (net (code "24") (name "BTN8_LED1") (class "Default")
      (node (ref "BTN8") (pin "LED1+") (pinfunction "LED1+_LED1+") (pintype "passive"))
      (node (ref "IC1") (pin "5") (pinfunction "QF_5") (pintype "tri_state"))
    )
    (net (code "25") (name "BTN8_LED2") (class "Default")
      (node (ref "BTN8") (pin "LED2+") (pinfunction "LED2+_LED2+") (pintype "passive"))
      (node (ref "IC1") (pin "15") (pinfunction "QA_15") (pintype "tri_state"))
    )
    (net (code "26") (name "CAN_H") (class "Default")
      (node (ref "BUS1") (pin "P$3") (pinfunction "1_P$3") (pintype "passive"))
      (node (ref "BUS2") (pin "P$3") (pinfunction "1_P$3") (pintype "passive"))
      (node (ref "D2") (pin "7") (pinfunction "CANH_7") (pintype "bidirectional"))
      (node (ref "TERM") (pin "3") (pinfunction "3_3") (pintype "passive"))
    )
    (net (code "27") (name "CAN_L") (class "Default")
      (node (ref "BUS1") (pin "P$2") (pinfunction "1_P$2") (pintype "passive"))
      (node (ref "BUS2") (pin "P$2") (pinfunction "1_P$2") (pintype "passive"))
      (node (ref "D2") (pin "6") (pinfunction "CANL_6") (pintype "bidirectional"))
      (node (ref "TERM") (pin "1") (pinfunction "1_1") (pintype "passive"))
    )
    (net (code "28") (name "CAN_RX") (class "Default")
      (node (ref "D2") (pin "4") (pinfunction "RXD_4") (pintype "output"))
      (node (ref "R14") (pin "1") (pinfunction "1_1") (pintype "passive"))
    )
    (net (code "29") (name "CAN_TX") (class "Default")
      (node (ref "D2") (pin "1") (pinfunction "TXD_1") (pintype "input"))
      (node (ref "R13") (pin "1") (pinfunction "1_1") (pintype "passive"))
    )
    (net (code "30") (name "CAN_VREF") (class "Default")
      (node (ref "C16") (pin "2") (pinfunction "P$2_2") (pintype "passive"))
      (node (ref "D2") (pin "5") (pinfunction "VREF_5") (pintype "output"))
      (node (ref "R3") (pin "2") (pinfunction "2_2") (pintype "passive"))
      (node (ref "R7") (pin "1") (pinfunction "1_1") (pintype "passive"))
    )
    (net (code "31") (name "DIN_4") (class "Default")
      (node (ref "IC4") (pin "14") (pinfunction "D_14") (pintype "tri_state"))
      (node (ref "R5") (pin "1") (pinfunction "1_1") (pintype "passive"))
    )
    (net (code "32") (name "DIN_8") (class "Default")
      (node (ref "IC4") (pin "6") (pinfunction "H_6") (pintype "tri_state"))
      (node (ref "R9") (pin "1") (pinfunction "1_1") (pintype "passive"))
    )
    (net (code "33") (name "FADER") (class "Default")
      (node (ref "C42") (pin "2") (pinfunction "P$2_2") (pintype "passive"))
      (node (ref "CPU1") (pin "22") (pinfunction "PA6/SPI1_MISO_22") (pintype "bidirectional"))
      (node (ref "FADER1") (pin "P2") (pinfunction "S_P2") (pintype "passive"))
    )
    (net (code "34") (name "GND") (class "Default")
      (node (ref "BTN1") (pin "SW1") (pinfunction "SW1_A_SW1") (pintype "passive"))
      (node (ref "BTN1") (pin "SW2") (pinfunction "SW1_B_SW2") (pintype "passive"))
      (node (ref "BTN2") (pin "SW1") (pinfunction "SW1_A_SW1") (pintype "passive"))
      (node (ref "BTN2") (pin "SW2") (pinfunction "SW1_B_SW2") (pintype "passive"))
      (node (ref "BTN3") (pin "SW1") (pinfunction "SW1_A_SW1") (pintype "passive"))
      (node (ref "BTN3") (pin "SW2") (pinfunction "SW1_B_SW2") (pintype "passive"))
      (node (ref "BTN4") (pin "SW1") (pinfunction "SW1_A_SW1") (pintype "passive"))
      (node (ref "BTN4") (pin "SW2") (pinfunction "SW1_B_SW2") (pintype "passive"))
      (node (ref "BTN5") (pin "SW1") (pinfunction "SW1_A_SW1") (pintype "passive"))
      (node (ref "BTN5") (pin "SW2") (pinfunction "SW1_B_SW2") (pintype "passive"))
      (node (ref "BTN6") (pin "SW1") (pinfunction "SW1_A_SW1") (pintype "passive"))
      (node (ref "BTN6") (pin "SW2") (pinfunction "SW1_B_SW2") (pintype "passive"))
      (node (ref "BTN7") (pin "SW1") (pinfunction "SW1_A_SW1") (pintype "passive"))
      (node (ref "BTN7") (pin "SW2") (pinfunction "SW1_B_SW2") (pintype "passive"))
      (node (ref "BTN8") (pin "SW1") (pinfunction "SW1_A_SW1") (pintype "passive"))
      (node (ref "BTN8") (pin "SW2") (pinfunction "SW1_B_SW2") (pintype "passive"))
      (node (ref "BUS1") (pin "P$4") (pinfunction "1_P$4") (pintype "passive"))
      (node (ref "BUS2") (pin "P$4") (pinfunction "1_P$4") (pintype "passive"))
      (node (ref "C1") (pin "1") (pinfunction "P$1_1") (pintype "passive"))
      (node (ref "C10") (pin "2") (pinfunction "P$2_2") (pintype "passive"))
      (node (ref "C11") (pin "2") (pinfunction "P$2_2") (pintype "passive"))
      (node (ref "C12") (pin "1") (pinfunction "P$1_1") (pintype "passive"))
      (node (ref "C13") (pin "2") (pinfunction "P$2_2") (pintype "passive"))
      (node (ref "C14") (pin "1") (pinfunction "P$1_1") (pintype "passive"))
      (node (ref "C15") (pin "1") (pinfunction "1_1") (pintype "passive"))
      (node (ref "C16") (pin "1") (pinfunction "P$1_1") (pintype "passive"))
      (node (ref "C17") (pin "1") (pinfunction "1_1") (pintype "passive"))
      (node (ref "C18") (pin "1") (pinfunction "1_1") (pintype "passive"))
      (node (ref "C19") (pin "2") (pinfunction "P$2_2") (pintype "passive"))
      (node (ref "C2") (pin "2") (pinfunction "P$2_2") (pintype "passive"))
      (node (ref "C20") (pin "1") (pinfunction "P$1_1") (pintype "passive"))
      (node (ref "C21") (pin "1") (pinfunction "P$1_1") (pintype "passive"))
      (node (ref "C22") (pin "1") (pinfunction "P$1_1") (pintype "passive"))
      (node (ref "C23") (pin "1") (pinfunction "P$1_1") (pintype "passive"))
      (node (ref "C24") (pin "1") (pinfunction "P$1_1") (pintype "passive"))
      (node (ref "C25") (pin "1") (pinfunction "P$1_1") (pintype "passive"))
      (node (ref "C26") (pin "1") (pinfunction "P$1_1") (pintype "passive"))
      (node (ref "C27") (pin "2") (pinfunction "P$2_2") (pintype "passive"))
      (node (ref "C28") (pin "2") (pinfunction "P$2_2") (pintype "passive"))
      (node (ref "C29") (pin "2") (pinfunction "P$2_2") (pintype "passive"))
      (node (ref "C3") (pin "1") (pinfunction "P$1_1") (pintype "passive"))
      (node (ref "C30") (pin "2") (pinfunction "P$2_2") (pintype "passive"))
      (node (ref "C31") (pin "1") (pinfunction "P$1_1") (pintype "passive"))
      (node (ref "C32") (pin "1") (pinfunction "P$1_1") (pintype "passive"))
      (node (ref "C33") (pin "1") (pinfunction "P$1_1") (pintype "passive"))
      (node (ref "C34") (pin "1") (pinfunction "P$1_1") (pintype "passive"))
      (node (ref "C35") (pin "1") (pinfunction "P$1_1") (pintype "passive"))
      (node (ref "C36") (pin "1") (pinfunction "P$1_1") (pintype "passive"))
      (node (ref "C37") (pin "1") (pinfunction "P$1_1") (pintype "passive"))
      (node (ref "C38") (pin "1") (pinfunction "P$1_1") (pintype "passive"))
      (node (ref "C39") (pin "1") (pinfunction "P$1_1") (pintype "passive"))
      (node (ref "C4") (pin "1") (pinfunction "P$1_1") (pintype "passive"))
      (node (ref "C40") (pin "1") (pinfunction "P$1_1") (pintype "passive"))
      (node (ref "C42") (pin "1") (pinfunction "P$1_1") (pintype "passive"))
      (node (ref "C43") (pin "1") (pinfunction "P$1_1") (pintype "passive"))
      (node (ref "C44") (pin "1") (pinfunction "P$1_1") (pintype "passive"))
      (node (ref "C45") (pin "1") (pinfunction "P$1_1") (pintype "passive"))
      (node (ref "C46") (pin "1") (pinfunction "P$1_1") (pintype "passive"))
      (node (ref "C47") (pin "1") (pinfunction "P$1_1") (pintype "passive"))
      (node (ref "C48") (pin "1") (pinfunction "P$1_1") (pintype "passive"))
      (node (ref "C49") (pin "1") (pinfunction "P$1_1") (pintype "passive"))
      (node (ref "C5") (pin "1") (pinfunction "P$1_1") (pintype "passive"))
      (node (ref "C6") (pin "1") (pinfunction "P$1_1") (pintype "passive"))
      (node (ref "C7") (pin "2") (pinfunction "P$2_2") (pintype "passive"))
      (node (ref "C8") (pin "2") (pinfunction "P$2_2") (pintype "passive"))
      (node (ref "C9") (pin "1") (pinfunction "P$1_1") (pintype "passive"))
      (node (ref "CPU1") (pin "12") (pinfunction "VSSA_12") (pintype "bidirectional"))
      (node (ref "CPU1") (pin "18") (pinfunction "VSS1_18") (pintype "bidirectional"))
      (node (ref "CPU1") (pin "63") (pinfunction "VSS2_63") (pintype "bidirectional"))
      (node (ref "D2") (pin "2") (pinfunction "GND_2") (pintype "power_in"))
      (node (ref "FADER1") (pin "P1") (pinfunction "A_P1") (pintype "passive"))
      (node (ref "IC1") (pin "13") (pinfunction "G_13") (pintype "input"))
      (node (ref "IC1") (pin "8") (pinfunction "GND_8") (pintype "power_in"))
      (node (ref "IC2") (pin "13") (pinfunction "G_13") (pintype "input"))
      (node (ref "IC2") (pin "8") (pinfunction "GND_8") (pintype "power_in"))
      (node (ref "IC3") (pin "13") (pinfunction "G_13") (pintype "input"))
      (node (ref "IC3") (pin "8") (pinfunction "GND_8") (pintype "power_in"))
      (node (ref "IC4") (pin "15") (pinfunction "CLK_INH_15") (pintype "input"))
      (node (ref "IC4") (pin "8") (pinfunction "GND_8") (pintype "power_in"))
      (node (ref "IC5") (pin "15") (pinfunction "CLK_INH_15") (pintype "input"))
      (node (ref "IC5") (pin "8") (pinfunction "GND_8") (pintype "power_in"))
      (node (ref "LCD") (pin "GND") (pinfunction "GND_GND") (pintype "bidirectional"))
      (node (ref "LED") (pin "C") (pinfunction "C_C") (pintype "passive"))
      (node (ref "POT1") (pin "CCW") (pinfunction "CCW_CCW") (pintype "passive"))
      (node (ref "POT2") (pin "CCW") (pinfunction "CCW_CCW") (pintype "passive"))
      (node (ref "POT3") (pin "CCW") (pinfunction "CCW_CCW") (pintype "passive"))
      (node (ref "POT4") (pin "CCW") (pinfunction "CCW_CCW") (pintype "passive"))
      (node (ref "POT5") (pin "CCW") (pinfunction "CCW_CCW") (pintype "passive"))
      (node (ref "POT6") (pin "CCW") (pinfunction "CCW_CCW") (pintype "passive"))
      (node (ref "POT7") (pin "CCW") (pinfunction "CCW_CCW") (pintype "passive"))
      (node (ref "PWR") (pin "C") (pinfunction "C_C") (pintype "passive"))
      (node (ref "R10") (pin "2") (pinfunction "2_2") (pintype "passive"))
      (node (ref "R12") (pin "2") (pinfunction "2_2") (pintype "passive"))
      (node (ref "R18") (pin "2") (pinfunction "2_2") (pintype "passive"))
      (node (ref "R19") (pin "2") (pinfunction "2_2") (pintype "passive"))
      (node (ref "R20") (pin "2") (pinfunction "2_2") (pintype "passive"))
      (node (ref "R21") (pin "2") (pinfunction "2_2") (pintype "passive"))
      (node (ref "R22") (pin "2") (pinfunction "2_2") (pintype "passive"))
      (node (ref "R23") (pin "2") (pinfunction "2_2") (pintype "passive"))
      (node (ref "R24") (pin "2") (pinfunction "2_2") (pintype "passive"))
      (node (ref "R25") (pin "2") (pinfunction "2_2") (pintype "passive"))
      (node (ref "R26") (pin "2") (pinfunction "2_2") (pintype "passive"))
      (node (ref "R27") (pin "2") (pinfunction "2_2") (pintype "passive"))
      (node (ref "R28") (pin "2") (pinfunction "2_2") (pintype "passive"))
      (node (ref "R29") (pin "2") (pinfunction "2_2") (pintype "passive"))
      (node (ref "R47") (pin "1") (pinfunction "1_1") (pintype "passive"))
      (node (ref "R48") (pin "1") (pinfunction "1_1") (pintype "passive"))
      (node (ref "R49") (pin "1") (pinfunction "1_1") (pintype "passive"))
      (node (ref "R50") (pin "1") (pinfunction "1_1") (pintype "passive"))
      (node (ref "R51") (pin "1") (pinfunction "1_1") (pintype "passive"))
      (node (ref "R52") (pin "1") (pinfunction "1_1") (pintype "passive"))
      (node (ref "R53") (pin "1") (pinfunction "1_1") (pintype "passive"))
      (node (ref "R54") (pin "1") (pinfunction "1_1") (pintype "passive"))
      (node (ref "R55") (pin "1") (pinfunction "1_1") (pintype "passive"))
      (node (ref "R56") (pin "1") (pinfunction "1_1") (pintype "passive"))
      (node (ref "ROT1") (pin "C") (pinfunction "COMMON_C") (pintype "input"))
      (node (ref "ROT1") (pin "S1") (pinfunction "SW1_S1") (pintype "bidirectional"))
      (node (ref "ROT2") (pin "C") (pinfunction "COMMON_C") (pintype "input"))
      (node (ref "ROT2") (pin "S1") (pinfunction "SW1_S1") (pintype "bidirectional"))
      (node (ref "T1") (pin "E") (pinfunction "E_E") (pintype "passive"))
      (node (ref "T2") (pin "E") (pinfunction "E_E") (pintype "passive"))
      (node (ref "TC1") (pin "3") (pinfunction "3_3") (pintype "passive"))
      (node (ref "TC1") (pin "5") (pinfunction "5_5") (pintype "passive"))
      (node (ref "TC1") (pin "9") (pinfunction "9_9") (pintype "passive"))
      (node (ref "U1") (pin "1") (pinfunction "ADJ_1") (pintype "input"))
    )
    (net (code "35") (name "LCD_CLK") (class "Default")
      (node (ref "CPU1") (pin "55") (pinfunction "PB3/JTDO_55") (pintype "bidirectional"))
      (node (ref "LCD") (pin "CLK") (pinfunction "CLK_CLK") (pintype "bidirectional"))
    )
    (net (code "36") (name "LCD_CS") (class "Default")
      (node (ref "CPU1") (pin "58") (pinfunction "PB6_58") (pintype "bidirectional"))
      (node (ref "LCD") (pin "CS") (pinfunction "CS_CS") (pintype "bidirectional"))
    )
    (net (code "37") (name "LCD_DC") (class "Default")
      (node (ref "CPU1") (pin "59") (pinfunction "PB7_59") (pintype "bidirectional"))
      (node (ref "LCD") (pin "DC") (pinfunction "DC_DC") (pintype "bidirectional"))
    )
    (net (code "38") (name "LCD_MISO_UNUSED") (class "Default")
      (node (ref "CPU1") (pin "56") (pinfunction "PB4/JTRST_56") (pintype "bidirectional"))
    )
    (net (code "39") (name "LCD_MOSI") (class "Default")
      (node (ref "CPU1") (pin "57") (pinfunction "PB5_57") (pintype "bidirectional"))
      (node (ref "LCD") (pin "MOSI") (pinfunction "MOSI_MOSI") (pintype "bidirectional"))
    )
    (net (code "40") (name "LCD_RST") (class "Default")
      (node (ref "CPU1") (pin "54") (pinfunction "PD2/SDIO_CMD_54") (pintype "bidirectional"))
      (node (ref "LCD") (pin "RES") (pinfunction "RST_RES") (pintype "bidirectional"))
    )
    (net (code "41") (name "NRST") (class "Default")
      (node (ref "CPU1") (pin "7") (pinfunction "NRST_7") (pintype "bidirectional"))
      (node (ref "TC1") (pin "10") (pinfunction "10_10") (pintype "passive"))
    )
    (net (code "42") (name "Net-(BTN1-PadLED1-)") (class "Default")
      (node (ref "BTN1") (pin "LED1-") (pinfunction "LED1-_LED1-") (pintype "passive"))
      (node (ref "R8") (pin "1") (pinfunction "1_1") (pintype "passive"))
    )
    (net (code "43") (name "Net-(BTN2-PadLED1-)") (class "Default")
      (node (ref "BTN2") (pin "LED1-") (pinfunction "LED1-_LED1-") (pintype "passive"))
      (node (ref "R15") (pin "1") (pinfunction "1_1") (pintype "passive"))
    )
    (net (code "44") (name "Net-(BTN3-PadLED1-)") (class "Default")
      (node (ref "BTN3") (pin "LED1-") (pinfunction "LED1-_LED1-") (pintype "passive"))
      (node (ref "R20") (pin "1") (pinfunction "1_1") (pintype "passive"))
    )
    (net (code "45") (name "Net-(BTN3-PadLED2-)") (class "Default")
      (node (ref "BTN3") (pin "LED2-") (pinfunction "LED2-_LED2-") (pintype "passive"))
      (node (ref "R21") (pin "1") (pinfunction "1_1") (pintype "passive"))
    )
    (net (code "46") (name "Net-(BTN4-PadLED1-)") (class "Default")
      (node (ref "BTN4") (pin "LED1-") (pinfunction "LED1-_LED1-") (pintype "passive"))
      (node (ref "R22") (pin "1") (pinfunction "1_1") (pintype "passive"))
    )
    (net (code "47") (name "Net-(BTN4-PadLED2-)") (class "Default")
      (node (ref "BTN4") (pin "LED2-") (pinfunction "LED2-_LED2-") (pintype "passive"))
      (node (ref "R23") (pin "1") (pinfunction "1_1") (pintype "passive"))
    )
    (net (code "48") (name "Net-(BTN5-PadLED1-)") (class "Default")
      (node (ref "BTN5") (pin "LED1-") (pinfunction "LED1-_LED1-") (pintype "passive"))
      (node (ref "R28") (pin "1") (pinfunction "1_1") (pintype "passive"))
    )
    (net (code "49") (name "Net-(BTN5-PadLED2-)") (class "Default")
      (node (ref "BTN5") (pin "LED2-") (pinfunction "LED2-_LED2-") (pintype "passive"))
      (node (ref "R29") (pin "1") (pinfunction "1_1") (pintype "passive"))
    )
    (net (code "50") (name "Net-(BTN6-PadLED1-)") (class "Default")
      (node (ref "BTN6") (pin "LED1-") (pinfunction "LED1-_LED1-") (pintype "passive"))
      (node (ref "R18") (pin "1") (pinfunction "1_1") (pintype "passive"))
    )
    (net (code "51") (name "Net-(BTN6-PadLED2-)") (class "Default")
      (node (ref "BTN6") (pin "LED2-") (pinfunction "LED2-_LED2-") (pintype "passive"))
      (node (ref "R19") (pin "1") (pinfunction "1_1") (pintype "passive"))
    )
    (net (code "52") (name "Net-(BTN7-PadLED1-)") (class "Default")
      (node (ref "BTN7") (pin "LED1-") (pinfunction "LED1-_LED1-") (pintype "passive"))
      (node (ref "R24") (pin "1") (pinfunction "1_1") (pintype "passive"))
    )
    (net (code "53") (name "Net-(BTN7-PadLED2-)") (class "Default")
      (node (ref "BTN7") (pin "LED2-") (pinfunction "LED2-_LED2-") (pintype "passive"))
      (node (ref "R25") (pin "1") (pinfunction "1_1") (pintype "passive"))
    )
    (net (code "54") (name "Net-(BTN8-PadLED1-)") (class "Default")
      (node (ref "BTN8") (pin "LED1-") (pinfunction "LED1-_LED1-") (pintype "passive"))
      (node (ref "R26") (pin "1") (pinfunction "1_1") (pintype "passive"))
    )
    (net (code "55") (name "Net-(BTN8-PadLED2-)") (class "Default")
      (node (ref "BTN8") (pin "LED2-") (pinfunction "LED2-_LED2-") (pintype "passive"))
      (node (ref "R27") (pin "1") (pinfunction "1_1") (pintype "passive"))
    )
    (net (code "56") (name "Net-(C5-P$2)") (class "Default")
      (node (ref "C5") (pin "2") (pinfunction "P$2_2") (pintype "passive"))
      (node (ref "CPU1") (pin "5") (pinfunction "PH0_5") (pintype "bidirectional"))
      (node (ref "U$19") (pin "P$2") (pinfunction "2_P$2") (pintype "passive"))
    )
    (net (code "57") (name "Net-(C6-P$2)") (class "Default")
      (node (ref "C6") (pin "2") (pinfunction "P$2_2") (pintype "passive"))
      (node (ref "CPU1") (pin "6") (pinfunction "PH1_6") (pintype "bidirectional"))
      (node (ref "U$19") (pin "P$1") (pinfunction "1_P$1") (pintype "passive"))
    )
    (net (code "58") (name "Net-(C7-P$1)") (class "Default")
      (node (ref "C7") (pin "1") (pinfunction "P$1_1") (pintype "passive"))
      (node (ref "CPU1") (pin "31") (pinfunction "VCAP1_31") (pintype "bidirectional"))
    )
    (net (code "59") (name "Net-(C13-P$1)") (class "Default")
      (node (ref "C13") (pin "1") (pinfunction "P$1_1") (pintype "passive"))
      (node (ref "CPU1") (pin "47") (pinfunction "VCAP2_47") (pintype "bidirectional"))
    )
    (net (code "60") (name "Net-(CPU1-BOOT0)") (class "Default")
      (node (ref "CPU1") (pin "60") (pinfunction "BOOT0_60") (pintype "bidirectional"))
      (node (ref "R12") (pin "1") (pinfunction "1_1") (pintype "passive"))
    )
    (net (code "61") (name "Net-(CPU1-PB8)") (class "Default")
      (node (ref "CPU1") (pin "61") (pinfunction "PB8_61") (pintype "bidirectional"))
      (node (ref "R14") (pin "2") (pinfunction "2_2") (pintype "passive"))
    )
    (net (code "62") (name "Net-(CPU1-PB9)") (class "Default")
      (node (ref "CPU1") (pin "62") (pinfunction "PB9_62") (pintype "bidirectional"))
      (node (ref "R13") (pin "2") (pinfunction "2_2") (pintype "passive"))
    )
    (net (code "63") (name "Net-(CPU1-PC12{slash}SDIO_CLK)") (class "Default")
      (node (ref "CPU1") (pin "53") (pinfunction "PC12/SDIO_CLK_53") (pintype "bidirectional"))
      (node (ref "R2") (pin "2") (pinfunction "2_2") (pintype "passive"))
    )
    (net (code "64") (name "Net-(D1A-A)") (class "Default")
      (node (ref "D1") (pin "1") (pinfunction "A_1") (pintype "passive"))
      (node (ref "IC2") (pin "6") (pinfunction "QG_6") (pintype "tri_state"))
    )
    (net (code "65") (name "Net-(D1A-C)") (class "Default")
      (node (ref "D1") (pin "20") (pinfunction "C_20") (pintype "passive"))
      (node (ref "R56") (pin "2") (pinfunction "2_2") (pintype "passive"))
    )
    (net (code "66") (name "Net-(D1B-A)") (class "Default")
      (node (ref "D1") (pin "2") (pinfunction "A_2") (pintype "passive"))
      (node (ref "IC2") (pin "7") (pinfunction "QH_7") (pintype "tri_state"))
    )
    (net (code "67") (name "Net-(D1B-C)") (class "Default")
      (node (ref "D1") (pin "19") (pinfunction "C_19") (pintype "passive"))
      (node (ref "R55") (pin "2") (pinfunction "2_2") (pintype "passive"))
    )
    (net (code "68") (name "Net-(D1C-A)") (class "Default")
      (node (ref "D1") (pin "3") (pinfunction "A_3") (pintype "passive"))
      (node (ref "IC3") (pin "15") (pinfunction "QA_15") (pintype "tri_state"))
    )
    (net (code "69") (name "Net-(D1C-C)") (class "Default")
      (node (ref "D1") (pin "18") (pinfunction "C_18") (pintype "passive"))
      (node (ref "R54") (pin "2") (pinfunction "2_2") (pintype "passive"))
    )
    (net (code "70") (name "Net-(D1D-A)") (class "Default")
      (node (ref "D1") (pin "4") (pinfunction "A_4") (pintype "passive"))
      (node (ref "IC3") (pin "1") (pinfunction "QB_1") (pintype "tri_state"))
    )
    (net (code "71") (name "Net-(D1D-C)") (class "Default")
      (node (ref "D1") (pin "17") (pinfunction "C_17") (pintype "passive"))
      (node (ref "R53") (pin "2") (pinfunction "2_2") (pintype "passive"))
    )
    (net (code "72") (name "Net-(D1E-A)") (class "Default")
      (node (ref "D1") (pin "5") (pinfunction "A_5") (pintype "passive"))
      (node (ref "IC3") (pin "2") (pinfunction "QC_2") (pintype "tri_state"))
    )
    (net (code "73") (name "Net-(D1E-C)") (class "Default")
      (node (ref "D1") (pin "16") (pinfunction "C_16") (pintype "passive"))
      (node (ref "R52") (pin "2") (pinfunction "2_2") (pintype "passive"))
    )
    (net (code "74") (name "Net-(D1F-A)") (class "Default")
      (node (ref "D1") (pin "6") (pinfunction "A_6") (pintype "passive"))
      (node (ref "IC3") (pin "3") (pinfunction "QD_3") (pintype "tri_state"))
    )
    (net (code "75") (name "Net-(D1F-C)") (class "Default")
      (node (ref "D1") (pin "15") (pinfunction "C_15") (pintype "passive"))
      (node (ref "R51") (pin "2") (pinfunction "2_2") (pintype "passive"))
    )
    (net (code "76") (name "Net-(D1G-A)") (class "Default")
      (node (ref "D1") (pin "7") (pinfunction "A_7") (pintype "passive"))
      (node (ref "IC3") (pin "4") (pinfunction "QE_4") (pintype "tri_state"))
    )
    (net (code "77") (name "Net-(D1G-C)") (class "Default")
      (node (ref "D1") (pin "14") (pinfunction "C_14") (pintype "passive"))
      (node (ref "R50") (pin "2") (pinfunction "2_2") (pintype "passive"))
    )
    (net (code "78") (name "Net-(D1H-A)") (class "Default")
      (node (ref "D1") (pin "8") (pinfunction "A_8") (pintype "passive"))
      (node (ref "IC3") (pin "5") (pinfunction "QF_5") (pintype "tri_state"))
    )
    (net (code "79") (name "Net-(D1H-C)") (class "Default")
      (node (ref "D1") (pin "13") (pinfunction "C_13") (pintype "passive"))
      (node (ref "R49") (pin "2") (pinfunction "2_2") (pintype "passive"))
    )
    (net (code "80") (name "Net-(D1I-A)") (class "Default")
      (node (ref "D1") (pin "9") (pinfunction "A_9") (pintype "passive"))
      (node (ref "IC3") (pin "6") (pinfunction "QG_6") (pintype "tri_state"))
    )
    (net (code "81") (name "Net-(D1I-C)") (class "Default")
      (node (ref "D1") (pin "12") (pinfunction "C_12") (pintype "passive"))
      (node (ref "R48") (pin "2") (pinfunction "2_2") (pintype "passive"))
    )
    (net (code "82") (name "Net-(D1J-A)") (class "Default")
      (node (ref "D1") (pin "10") (pinfunction "A_10") (pintype "passive"))
      (node (ref "IC3") (pin "7") (pinfunction "QH_7") (pintype "tri_state"))
    )
    (net (code "83") (name "Net-(D1J-C)") (class "Default")
      (node (ref "D1") (pin "11") (pinfunction "C_11") (pintype "passive"))
      (node (ref "R47") (pin "2") (pinfunction "2_2") (pintype "passive"))
    )
    (net (code "84") (name "Net-(D2-RS)") (class "Default")
      (node (ref "D2") (pin "8") (pinfunction "RS_8") (pintype "input"))
      (node (ref "R10") (pin "1") (pinfunction "1_1") (pintype "passive"))
    )
    (net (code "85") (name "Net-(IC1-SER)") (class "Default")
      (node (ref "IC1") (pin "14") (pinfunction "SER_14") (pintype "input"))
      (node (ref "IC2") (pin "9") (pinfunction "QH*_9") (pintype "tri_state"))
    )
    (net (code "86") (name "Net-(IC2-SER)") (class "Default")
      (node (ref "IC2") (pin "14") (pinfunction "SER_14") (pintype "input"))
      (node (ref "IC3") (pin "9") (pinfunction "QH*_9") (pintype "tri_state"))
    )
    (net (code "87") (name "Net-(IC4-SER)") (class "Default")
      (node (ref "IC4") (pin "10") (pinfunction "SER_10") (pintype "input"))
      (node (ref "IC5") (pin "9") (pinfunction "QH_9") (pintype "tri_state"))
      (node (ref "R38") (pin "1") (pinfunction "1_1") (pintype "passive"))
    )
    (net (code "88") (name "Net-(IC5-SER)") (class "Default")
      (node (ref "IC5") (pin "10") (pinfunction "SER_10") (pintype "input"))
      (node (ref "R1") (pin "1") (pinfunction "1_1") (pintype "passive"))
    )
    (net (code "89") (name "Net-(LED-PadA)") (class "Default")
      (node (ref "LED") (pin "A") (pinfunction "A_A") (pintype "passive"))
      (node (ref "R2") (pin "1") (pinfunction "1_1") (pintype "passive"))
    )
    (net (code "90") (name "Net-(PWR-PadA)") (class "Default")
      (node (ref "PWR") (pin "A") (pinfunction "A_A") (pintype "passive"))
      (node (ref "R17") (pin "1") (pinfunction "1_1") (pintype "passive"))
    )
    (net (code "91") (name "Net-(R3-Pad1)") (class "Default")
      (node (ref "R3") (pin "1") (pinfunction "1_1") (pintype "passive"))
      (node (ref "TERM") (pin "4") (pinfunction "4_4") (pintype "passive"))
    )
    (net (code "92") (name "Net-(R7-Pad2)") (class "Default")
      (node (ref "R7") (pin "2") (pinfunction "2_2") (pintype "passive"))
      (node (ref "TERM") (pin "2") (pinfunction "2_2") (pintype "passive"))
    )
    (net (code "93") (name "Net-(R8-Pad2)") (class "Default")
      (node (ref "R8") (pin "2") (pinfunction "2_2") (pintype "passive"))
      (node (ref "T1") (pin "C") (pinfunction "C_C") (pintype "passive"))
    )
    (net (code "94") (name "Net-(R11-Pad2)") (class "Default")
      (node (ref "R11") (pin "2") (pinfunction "2_2") (pintype "passive"))
      (node (ref "T1") (pin "B") (pinfunction "B_B") (pintype "passive"))
    )
    (net (code "95") (name "Net-(R15-Pad2)") (class "Default")
      (node (ref "R15") (pin "2") (pinfunction "2_2") (pintype "passive"))
      (node (ref "T2") (pin "C") (pinfunction "C_C") (pintype "passive"))
    )
    (net (code "96") (name "Net-(R16-Pad2)") (class "Default")
      (node (ref "R16") (pin "2") (pinfunction "2_2") (pintype "passive"))
      (node (ref "T2") (pin "B") (pinfunction "B_B") (pintype "passive"))
    )
    (net (code "97") (name "Net-(ROT1-CH_A)") (class "Default")
      (node (ref "R39") (pin "2") (pinfunction "2_2") (pintype "passive"))
      (node (ref "R41") (pin "2") (pinfunction "2_2") (pintype "passive"))
      (node (ref "ROT1") (pin "A") (pinfunction "CH_A_A") (pintype "output"))
    )
    (net (code "98") (name "Net-(ROT1-CH_B)") (class "Default")
      (node (ref "R40") (pin "2") (pinfunction "2_2") (pintype "passive"))
      (node (ref "R42") (pin "2") (pinfunction "2_2") (pintype "passive"))
      (node (ref "ROT1") (pin "B") (pinfunction "CH_B_B") (pintype "output"))
    )
    (net (code "99") (name "Net-(ROT2-CH_A)") (class "Default")
      (node (ref "R43") (pin "2") (pinfunction "2_2") (pintype "passive"))
      (node (ref "R45") (pin "2") (pinfunction "2_2") (pintype "passive"))
      (node (ref "ROT2") (pin "A") (pinfunction "CH_A_A") (pintype "output"))
    )
    (net (code "100") (name "Net-(ROT2-CH_B)") (class "Default")
      (node (ref "R44") (pin "2") (pinfunction "2_2") (pintype "passive"))
      (node (ref "R46") (pin "2") (pinfunction "2_2") (pintype "passive"))
      (node (ref "ROT2") (pin "B") (pinfunction "CH_B_B") (pintype "output"))
    )
    (net (code "101") (name "POT1") (class "Default")
      (node (ref "C46") (pin "2") (pinfunction "P$2_2") (pintype "passive"))
      (node (ref "CPU1") (pin "14") (pinfunction "PA0_14") (pintype "bidirectional"))
      (node (ref "POT1") (pin "CENTER") (pinfunction "WIPER_CENTER") (pintype "passive"))
    )
    (net (code "102") (name "POT2") (class "Default")
      (node (ref "C49") (pin "2") (pinfunction "P$2_2") (pintype "passive"))
      (node (ref "CPU1") (pin "17") (pinfunction "PA3/UART2_RX_17") (pintype "bidirectional"))
      (node (ref "POT2") (pin "CENTER") (pinfunction "WIPER_CENTER") (pintype "passive"))
    )
    (net (code "103") (name "POT3") (class "Default")
      (node (ref "C45") (pin "2") (pinfunction "P$2_2") (pintype "passive"))
      (node (ref "CPU1") (pin "15") (pinfunction "PA1_15") (pintype "bidirectional"))
      (node (ref "POT3") (pin "CENTER") (pinfunction "WIPER_CENTER") (pintype "passive"))
    )
    (net (code "104") (name "POT4") (class "Default")
      (node (ref "C48") (pin "2") (pinfunction "P$2_2") (pintype "passive"))
      (node (ref "CPU1") (pin "16") (pinfunction "PA2/UART2_TX_16") (pintype "bidirectional"))
      (node (ref "POT4") (pin "CENTER") (pinfunction "WIPER_CENTER") (pintype "passive"))
    )
    (net (code "105") (name "POT5") (class "Default")
      (node (ref "C44") (pin "2") (pinfunction "P$2_2") (pintype "passive"))
      (node (ref "CPU1") (pin "23") (pinfunction "PA7/SPI1_MOSI_23") (pintype "bidirectional"))
      (node (ref "POT5") (pin "CENTER") (pinfunction "WIPER_CENTER") (pintype "passive"))
    )
    (net (code "106") (name "POT6") (class "Default")
      (node (ref "C47") (pin "2") (pinfunction "P$2_2") (pintype "passive"))
      (node (ref "CPU1") (pin "20") (pinfunction "PA4/SPI1_NSS_20") (pintype "bidirectional"))
      (node (ref "POT6") (pin "CENTER") (pinfunction "WIPER_CENTER") (pintype "passive"))
    )
    (net (code "107") (name "POT7") (class "Default")
      (node (ref "C43") (pin "2") (pinfunction "P$2_2") (pintype "passive"))
      (node (ref "CPU1") (pin "21") (pinfunction "PA5/SPI1_SCK_21") (pintype "bidirectional"))
      (node (ref "POT7") (pin "CENTER") (pinfunction "WIPER_CENTER") (pintype "passive"))
    )
    (net (code "108") (name "ROT1_A") (class "Default")
      (node (ref "C27") (pin "1") (pinfunction "P$1_1") (pintype "passive"))
      (node (ref "IC4") (pin "4") (pinfunction "F_4") (pintype "tri_state"))
      (node (ref "R39") (pin "1") (pinfunction "1_1") (pintype "passive"))
    )
    (net (code "109") (name "ROT1_B") (class "Default")
      (node (ref "C28") (pin "1") (pinfunction "P$1_1") (pintype "passive"))
      (node (ref "IC4") (pin "5") (pinfunction "G_5") (pintype "tri_state"))
      (node (ref "R40") (pin "1") (pinfunction "1_1") (pintype "passive"))
    )
    (net (code "110") (name "ROT1_SW") (class "Default")
      (node (ref "IC4") (pin "3") (pinfunction "E_3") (pintype "tri_state"))
      (node (ref "R6") (pin "1") (pinfunction "1_1") (pintype "passive"))
      (node (ref "ROT1") (pin "S2") (pinfunction "SW2_S2") (pintype "bidirectional"))
    )
    (net (code "111") (name "ROT2_A") (class "Default")
      (node (ref "C29") (pin "1") (pinfunction "P$1_1") (pintype "passive"))
      (node (ref "IC4") (pin "11") (pinfunction "A_11") (pintype "tri_state"))
      (node (ref "R43") (pin "1") (pinfunction "1_1") (pintype "passive"))
    )
    (net (code "112") (name "ROT2_B") (class "Default")
      (node (ref "C30") (pin "1") (pinfunction "P$1_1") (pintype "passive"))
      (node (ref "IC4") (pin "12") (pinfunction "B_12") (pintype "tri_state"))
      (node (ref "R44") (pin "1") (pinfunction "1_1") (pintype "passive"))
    )
    (net (code "113") (name "ROT2_SW") (class "Default")
      (node (ref "IC4") (pin "13") (pinfunction "C_13") (pintype "tri_state"))
      (node (ref "R4") (pin "1") (pinfunction "1_1") (pintype "passive"))
      (node (ref "ROT2") (pin "S2") (pinfunction "SW2_S2") (pintype "bidirectional"))
    )
    (net (code "114") (name "SPI2_CLK") (class "Default")
      (node (ref "CPU1") (pin "34") (pinfunction "PB13/I2S2_CK_34") (pintype "bidirectional"))
      (node (ref "IC1") (pin "11") (pinfunction "SCK_11") (pintype "input"))
      (node (ref "IC2") (pin "11") (pinfunction "SCK_11") (pintype "input"))
      (node (ref "IC3") (pin "11") (pinfunction "SCK_11") (pintype "input"))
      (node (ref "IC4") (pin "2") (pinfunction "CLK_2") (pintype "input"))
      (node (ref "IC5") (pin "2") (pinfunction "CLK_2") (pintype "input"))
    )
    (net (code "115") (name "SPI2_MISO") (class "Default")
      (node (ref "CPU1") (pin "35") (pinfunction "PB14/I2S2_XD_35") (pintype "bidirectional"))
      (node (ref "IC4") (pin "9") (pinfunction "QH_9") (pintype "tri_state"))
    )
    (net (code "116") (name "SPI2_MOSI") (class "Default")
      (node (ref "CPU1") (pin "36") (pinfunction "PB15/I2S2_SD_36") (pintype "bidirectional"))
      (node (ref "IC3") (pin "14") (pinfunction "SER_14") (pintype "input"))
    )
    (net (code "117") (name "SPI2_RC1") (class "Default")
      (node (ref "CPU1") (pin "11") (pinfunction "PC3_11") (pintype "bidirectional"))
      (node (ref "IC1") (pin "12") (pinfunction "RCK_12") (pintype "input"))
      (node (ref "IC2") (pin "12") (pinfunction "RCK_12") (pintype "input"))
      (node (ref "IC3") (pin "12") (pinfunction "RCK_12") (pintype "input"))
    )
    (net (code "118") (name "SPI2_RC2") (class "Default")
      (node (ref "CPU1") (pin "10") (pinfunction "PC2_10") (pintype "bidirectional"))
      (node (ref "IC4") (pin "1") (pinfunction "SH/~{LD}_1") (pintype "input"))
      (node (ref "IC5") (pin "1") (pinfunction "SH/~{LD}_1") (pintype "input"))
    )
    (net (code "119") (name "SWCK") (class "Default")
      (node (ref "CPU1") (pin "49") (pinfunction "PA14/JTCK_49") (pintype "bidirectional"))
      (node (ref "TC1") (pin "4") (pinfunction "4_4") (pintype "passive"))
    )
    (net (code "120") (name "SWDIO") (class "Default")
      (node (ref "CPU1") (pin "46") (pinfunction "PA13/JTMS_46") (pintype "bidirectional"))
      (node (ref "TC1") (pin "2") (pinfunction "2_2") (pintype "passive"))
    )
    (net (code "121") (name "UART_RX") (class "Default")
      (node (ref "CPU1") (pin "52") (pinfunction "PC11/SDIO_D3_52") (pintype "bidirectional"))
      (node (ref "TC1") (pin "8") (pinfunction "8_8") (pintype "passive"))
    )
    (net (code "122") (name "UART_TX") (class "Default")
      (node (ref "CPU1") (pin "51") (pinfunction "PC10/SDIO_D2_51") (pintype "bidirectional"))
      (node (ref "TC1") (pin "6") (pinfunction "6_6") (pintype "passive"))
    )
    (net (code "123") (name "unconnected-(CPU1-PA8-Pad41)") (class "Default")
      (node (ref "CPU1") (pin "41") (pinfunction "PA8_41") (pintype "bidirectional"))
    )
    (net (code "124") (name "unconnected-(CPU1-PA9{slash}UART1_TX-Pad42)") (class "Default")
      (node (ref "CPU1") (pin "42") (pinfunction "PA9/UART1_TX_42") (pintype "bidirectional"))
    )
    (net (code "125") (name "unconnected-(CPU1-PA10{slash}UART1_RX-Pad43)") (class "Default")
      (node (ref "CPU1") (pin "43") (pinfunction "PA10/UART1_RX_43") (pintype "bidirectional"))
    )
    (net (code "126") (name "unconnected-(CPU1-PA11-Pad44)") (class "Default")
      (node (ref "CPU1") (pin "44") (pinfunction "PA11_44") (pintype "bidirectional"))
    )
    (net (code "127") (name "unconnected-(CPU1-PA12-Pad45)") (class "Default")
      (node (ref "CPU1") (pin "45") (pinfunction "PA12_45") (pintype "bidirectional"))
    )
    (net (code "128") (name "unconnected-(CPU1-PA15{slash}JTDI-Pad50)") (class "Default")
      (node (ref "CPU1") (pin "50") (pinfunction "PA15/JTDI_50") (pintype "bidirectional"))
    )
    (net (code "129") (name "unconnected-(CPU1-PB0-Pad26)") (class "Default")
      (node (ref "CPU1") (pin "26") (pinfunction "PB0_26") (pintype "bidirectional"))
    )
    (net (code "130") (name "unconnected-(CPU1-PB1-Pad27)") (class "Default")
      (node (ref "CPU1") (pin "27") (pinfunction "PB1_27") (pintype "bidirectional"))
    )
    (net (code "131") (name "unconnected-(CPU1-PB2-BOOT1-Pad28)") (class "Default")
      (node (ref "CPU1") (pin "28") (pinfunction "PB2-BOOT1_28") (pintype "bidirectional"))
    )
    (net (code "132") (name "unconnected-(CPU1-PB10-Pad29)") (class "Default")
      (node (ref "CPU1") (pin "29") (pinfunction "PB10_29") (pintype "bidirectional"))
    )
    (net (code "133") (name "unconnected-(CPU1-PB11-Pad30)") (class "Default")
      (node (ref "CPU1") (pin "30") (pinfunction "PB11_30") (pintype "bidirectional"))
    )
    (net (code "134") (name "unconnected-(CPU1-PB12{slash}I2S2_WS-Pad33)") (class "Default")
      (node (ref "CPU1") (pin "33") (pinfunction "PB12/I2S2_WS_33") (pintype "bidirectional"))
    )
    (net (code "135") (name "unconnected-(CPU1-PC0-Pad8)") (class "Default")
      (node (ref "CPU1") (pin "8") (pinfunction "PC0_8") (pintype "bidirectional"))
    )
    (net (code "136") (name "unconnected-(CPU1-PC1-Pad9)") (class "Default")
      (node (ref "CPU1") (pin "9") (pinfunction "PC1_9") (pintype "bidirectional"))
    )
    (net (code "137") (name "unconnected-(CPU1-PC4-Pad24)") (class "Default")
      (node (ref "CPU1") (pin "24") (pinfunction "PC4_24") (pintype "bidirectional"))
    )
    (net (code "138") (name "unconnected-(CPU1-PC5-Pad25)") (class "Default")
      (node (ref "CPU1") (pin "25") (pinfunction "PC5_25") (pintype "bidirectional"))
    )
    (net (code "139") (name "unconnected-(CPU1-PC6{slash}I2S2_MCK-Pad37)") (class "Default")
      (node (ref "CPU1") (pin "37") (pinfunction "PC6/I2S2_MCK_37") (pintype "bidirectional"))
    )
    (net (code "140") (name "unconnected-(CPU1-PC7-Pad38)") (class "Default")
      (node (ref "CPU1") (pin "38") (pinfunction "PC7_38") (pintype "bidirectional"))
    )
    (net (code "141") (name "unconnected-(CPU1-PC8{slash}SDIO_D0-Pad39)") (class "Default")
      (node (ref "CPU1") (pin "39") (pinfunction "PC8/SDIO_D0_39") (pintype "bidirectional"))
    )
    (net (code "142") (name "unconnected-(CPU1-PC9{slash}SDIO_D1-Pad40)") (class "Default")
      (node (ref "CPU1") (pin "40") (pinfunction "PC9/SDIO_D1_40") (pintype "bidirectional"))
    )
    (net (code "143") (name "unconnected-(CPU1-PC13-Pad2)") (class "Default")
      (node (ref "CPU1") (pin "2") (pinfunction "PC13_2") (pintype "bidirectional"))
    )
    (net (code "144") (name "unconnected-(CPU1-PC14-Pad3)") (class "Default")
      (node (ref "CPU1") (pin "3") (pinfunction "PC14_3") (pintype "bidirectional"))
    )
    (net (code "145") (name "unconnected-(CPU1-PC15-Pad4)") (class "Default")
      (node (ref "CPU1") (pin "4") (pinfunction "PC15_4") (pintype "bidirectional"))
    )
    (net (code "146") (name "unconnected-(IC1-QH*-Pad9)") (class "Default")
      (node (ref "IC1") (pin "9") (pinfunction "QH*_9") (pintype "tri_state"))
    )
    (net (code "147") (name "unconnected-(IC4-~{QH}-Pad7)") (class "Default")
      (node (ref "IC4") (pin "7") (pinfunction "~{QH}_7") (pintype "input"))
    )
    (net (code "148") (name "unconnected-(IC5-~{QH}-Pad7)") (class "Default")
      (node (ref "IC5") (pin "7") (pinfunction "~{QH}_7") (pintype "input"))
    )
    (net (code "149") (name "unconnected-(POT1-CHASSIS-Pad4)") (class "Default")
      (node (ref "POT1") (pin "4") (pinfunction "CHASSIS_4") (pintype "passive"))
    )
    (net (code "150") (name "unconnected-(POT2-CHASSIS-Pad4)") (class "Default")
      (node (ref "POT2") (pin "4") (pinfunction "CHASSIS_4") (pintype "passive"))
    )
    (net (code "151") (name "unconnected-(POT3-CHASSIS-Pad4)") (class "Default")
      (node (ref "POT3") (pin "4") (pinfunction "CHASSIS_4") (pintype "passive"))
    )
    (net (code "152") (name "unconnected-(POT4-CHASSIS-Pad4)") (class "Default")
      (node (ref "POT4") (pin "4") (pinfunction "CHASSIS_4") (pintype "passive"))
    )
    (net (code "153") (name "unconnected-(POT5-CHASSIS-Pad4)") (class "Default")
      (node (ref "POT5") (pin "4") (pinfunction "CHASSIS_4") (pintype "passive"))
    )
    (net (code "154") (name "unconnected-(POT6-CHASSIS-Pad4)") (class "Default")
      (node (ref "POT6") (pin "4") (pinfunction "CHASSIS_4") (pintype "passive"))
    )
    (net (code "155") (name "unconnected-(POT7-CHASSIS-Pad4)") (class "Default")
      (node (ref "POT7") (pin "4") (pinfunction "CHASSIS_4") (pintype "passive"))
    )
    (net (code "156") (name "unconnected-(TC1-Pad7)") (class "Default")
      (node (ref "TC1") (pin "7") (pinfunction "7_7") (pintype "passive"))
    )
  )
)
